# TOP.net
KiCad netlist of a schematic drawn in Altium Designer
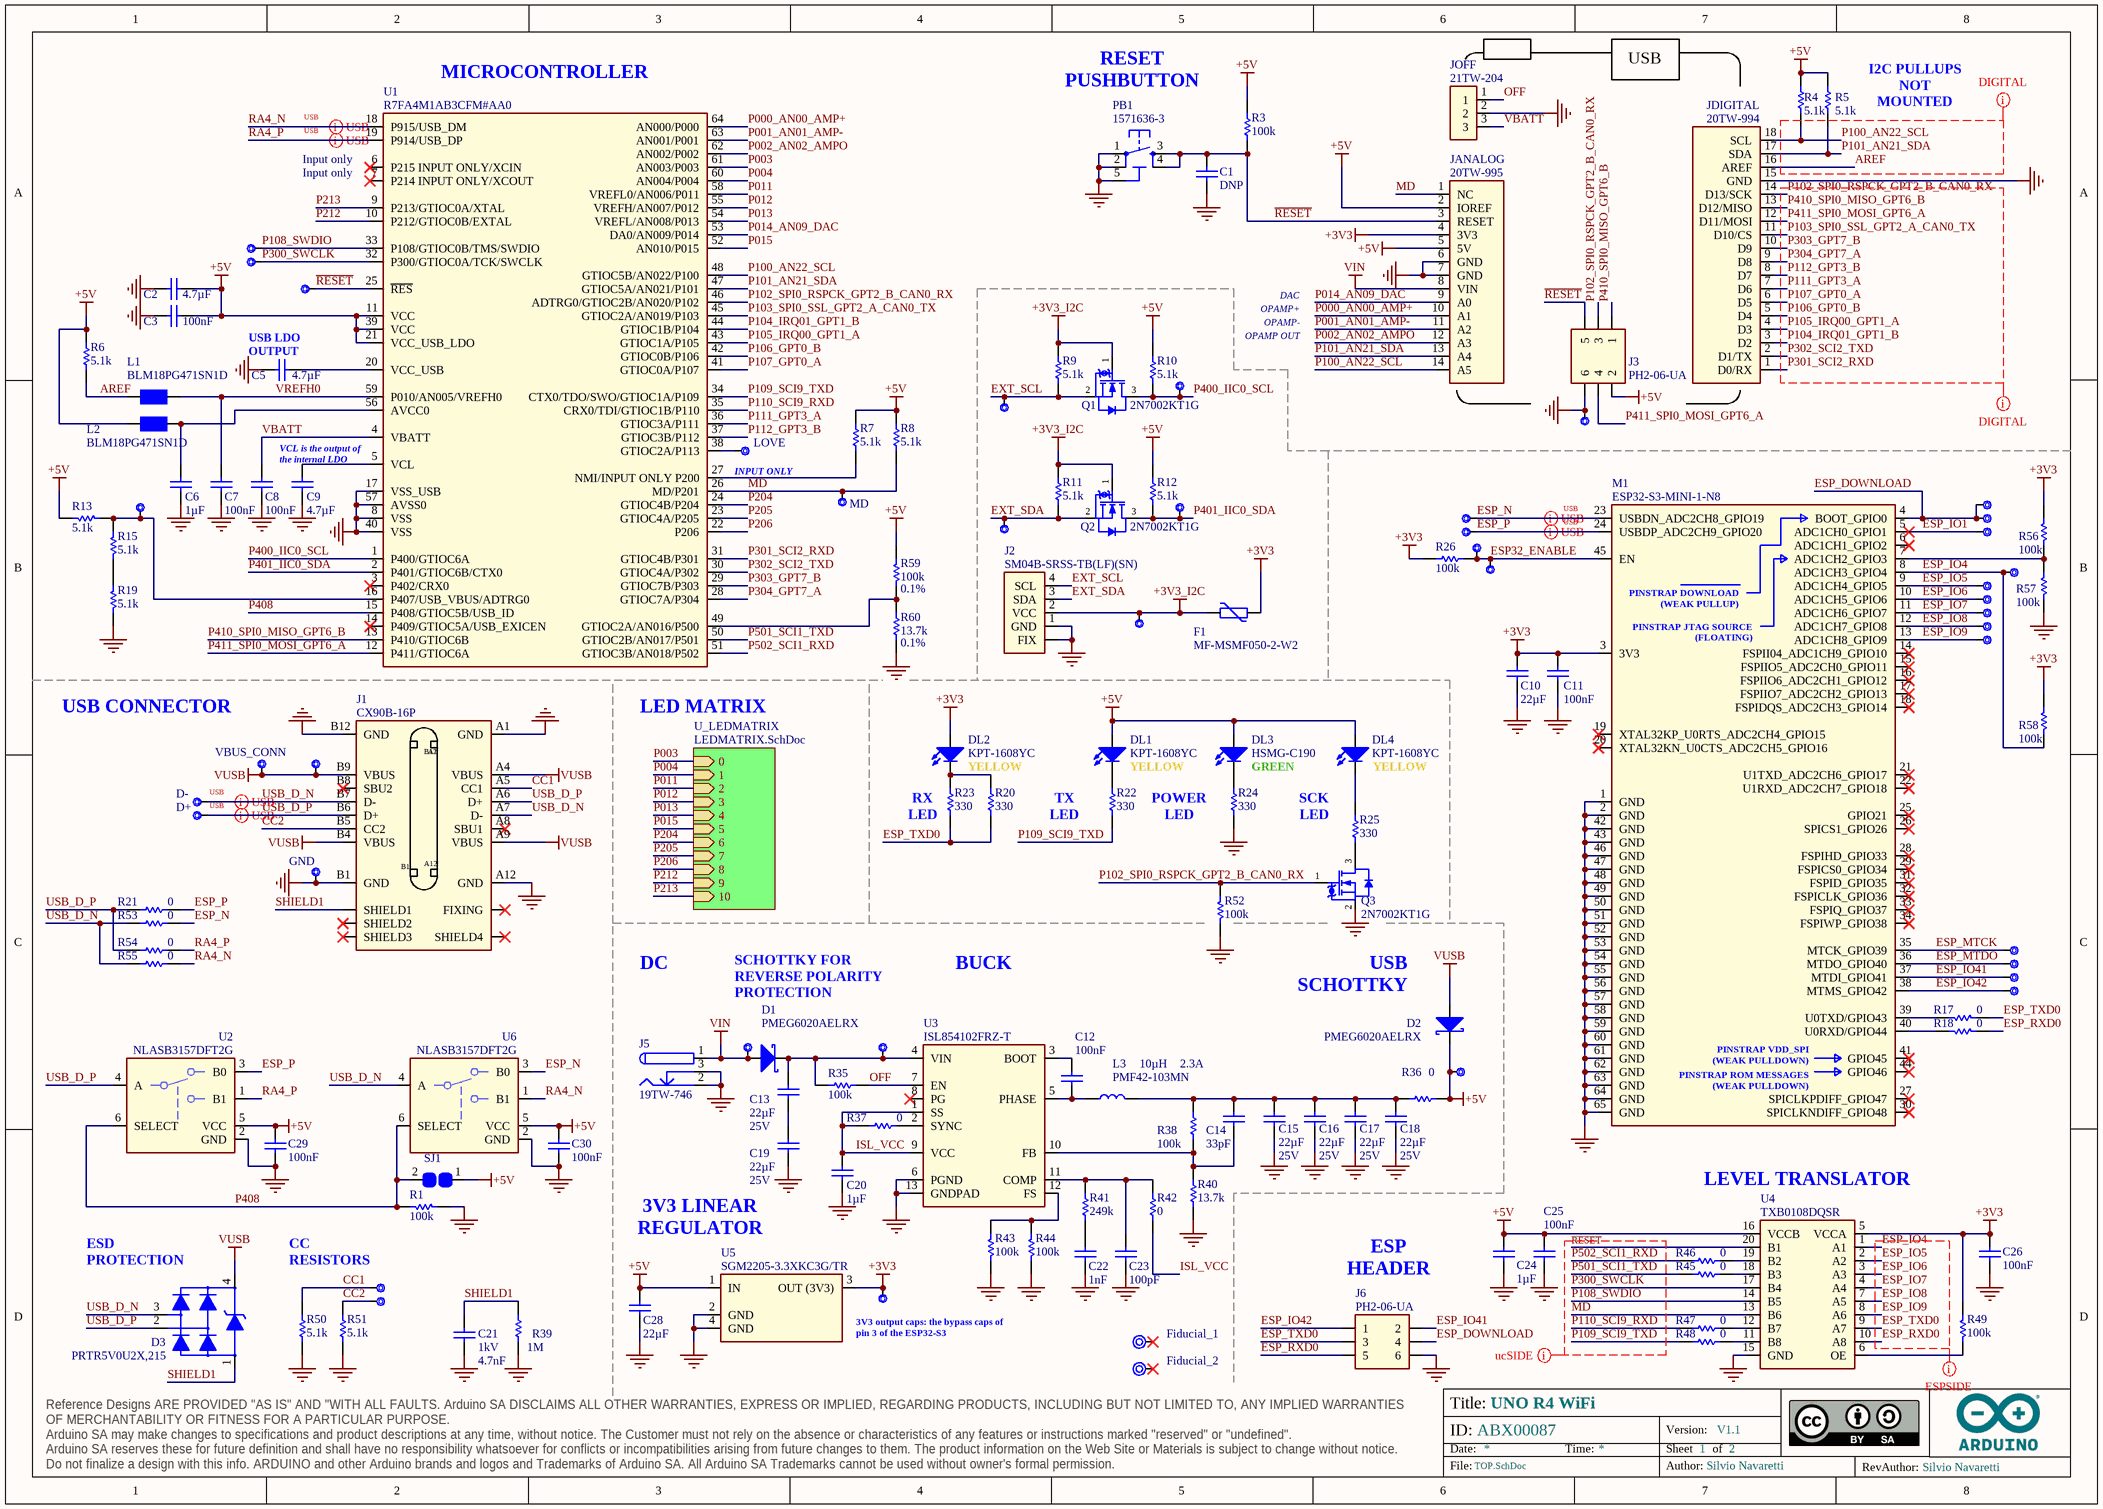
[diagram p0: TOP.SchDoc]

(export (version "E")
  (design (tool "Eeschema 10.0.6"))
  (components
    (comp (ref "3V3_IC")
      (value "CMP-018-0004-A.4")
      (footprint "TP-0.8MM")
      (description "Test point 0.8mm")
      (libsource (lib "Clean") (part "TESTPOINT"))
    )
    (comp (ref "3V3_TOP")
      (value "CMP-018-0004-A.4")
      (footprint "TP-0.8MM")
      (description "Test point 0.8mm")
      (libsource (lib "Clean") (part "TESTPOINT"))
    )
    (comp (ref "5V_TOP")
      (value "CMP-018-0004-A.4")
      (footprint "TP-0.8MM")
      (description "Test point 0.8mm")
      (libsource (lib "Clean") (part "TESTPOINT"))
    )
    (comp (ref "BUCK_IN_TOP")
      (value "CMP-018-0004-A.4")
      (footprint "TP-0.8MM")
      (description "Test point 0.8mm")
      (libsource (lib "Clean") (part "TESTPOINT"))
    )
    (comp (ref "C1") (value "DNP") (footprint "CAP-0402") (libsource (lib "Clean") (part "DNP")))
    (comp (ref "C2")
      (value "4.7µF")
      (footprint "CAP-0603")
      (description "CAP CHIP 0603 4.7uF 10% 16V X5R")
      (fields (field (name "TOLERANCE") "10%") (field (name "MANUFACTURER") "Murata"))
      (libsource (lib "Clean") (part "CAP"))
    )
    (comp (ref "C3")
      (value "100nF")
      (footprint "CAP-0402")
      (description "CAP CHIP 0402 100nF 10% 50V X5R")
      (fields (field (name "TOLERANCE") "10%") (field (name "MANUFACTURER") "Murata"))
      (libsource (lib "Clean") (part "CAP"))
    )
    (comp (ref "C5")
      (value "4.7µF")
      (footprint "CAP-0603")
      (description "CAP CHIP 0603 4.7uF 10% 16V X5R")
      (fields (field (name "TOLERANCE") "10%") (field (name "MANUFACTURER") "Murata"))
      (libsource (lib "Clean") (part "CAP"))
    )
    (comp (ref "C6")
      (value "1µF")
      (footprint "CAP-0402")
      (description "CAP CHIP 0402 1uF 10% 10V X5R")
      (fields (field (name "TOLERANCE") "10%") (field (name "PART NUMBER") "CL05A105KP5NNNC"))
      (libsource (lib "Clean") (part "CAP"))
    )
    (comp (ref "C7")
      (value "100nF")
      (footprint "CAP-0402")
      (description "CAP CHIP 0402 100nF 10% 50V X5R")
      (fields (field (name "TOLERANCE") "10%") (field (name "MANUFACTURER") "Murata"))
      (libsource (lib "Clean") (part "CAP"))
    )
    (comp (ref "C8")
      (value "100nF")
      (footprint "CAP-0402")
      (description "CAP CHIP 0402 100nF 10% 50V X5R")
      (fields (field (name "TOLERANCE") "10%") (field (name "MANUFACTURER") "Murata"))
      (libsource (lib "Clean") (part "CAP"))
    )
    (comp (ref "C9")
      (value "4.7µF")
      (footprint "CAP-0603")
      (description "CAP CHIP 0603 4.7uF 10% 16V X5R")
      (fields (field (name "TOLERANCE") "10%") (field (name "MANUFACTURER") "Murata"))
      (libsource (lib "Clean") (part "CAP"))
    )
    (comp (ref "C10")
      (value "22µF")
      (footprint "CAP-0805")
      (description "CAP CHIP 0805 22uF 20% 25V X5R")
      (fields (field (name "VOLTAGE") "25V") (field (name "TOLERANCE") "20%"))
      (libsource (lib "Clean") (part "CAP"))
    )
    (comp (ref "C11")
      (value "100nF")
      (footprint "CAP-0402")
      (description "CAP CHIP 0402 100nF 10% 50V X5R")
      (fields (field (name "TOLERANCE") "10%") (field (name "MANUFACTURER") "Murata"))
      (libsource (lib "Clean") (part "CAP"))
    )
    (comp (ref "C12")
      (value "100nF")
      (footprint "CAP-0402")
      (description "CAP CHIP 0402 100nF 10% 50V X5R")
      (fields (field (name "TOLERANCE") "10%") (field (name "MANUFACTURER") "Murata"))
      (libsource (lib "Clean") (part "CAP"))
    )
    (comp (ref "C13")
      (value "22µF")
      (footprint "CAP-0805")
      (description "CAP CHIP 0805 22uF 20% 25V X5R")
      (fields
        (field (name "PART NUMBER") "CL21A226MAQNNNE")
        (field (name "TOLERANCE") "20%")
        (field (name "VOLTAGE") "25V")
      )
      (libsource (lib "Clean") (part "CAP"))
    )
    (comp (ref "C14")
      (value "33pF")
      (footprint "CAP-0402")
      (description "CAP CHIP 0402 33pF 5% 50V C0G")
      (fields (field (name "MANUFACTURER") "Murata") (field (name "VOLTAGE") "50V"))
      (libsource (lib "Clean") (part "CAP"))
    )
    (comp (ref "C15")
      (value "22µF")
      (footprint "CAP-0805")
      (description "CAP CHIP 0805 22uF 20% 25V X5R")
      (fields
        (field (name "PART NUMBER") "CL21A226MAQNNNE")
        (field (name "TOLERANCE") "20%")
        (field (name "VOLTAGE") "25V")
      )
      (libsource (lib "Clean") (part "CAP"))
    )
    (comp (ref "C16")
      (value "22µF")
      (footprint "CAP-0805")
      (description "CAP CHIP 0805 22uF 20% 25V X5R")
      (fields
        (field (name "PART NUMBER") "CL21A226MAQNNNE")
        (field (name "TOLERANCE") "20%")
        (field (name "VOLTAGE") "25V")
      )
      (libsource (lib "Clean") (part "CAP"))
    )
    (comp (ref "C17")
      (value "22µF")
      (footprint "CAP-0805")
      (description "CAP CHIP 0805 22uF 20% 25V X5R")
      (fields
        (field (name "PART NUMBER") "CL21A226MAQNNNE")
        (field (name "TOLERANCE") "20%")
        (field (name "VOLTAGE") "25V")
      )
      (libsource (lib "Clean") (part "CAP"))
    )
    (comp (ref "C18")
      (value "22µF")
      (footprint "CAP-0805")
      (description "CAP CHIP 0805 22uF 20% 25V X5R")
      (fields
        (field (name "PART NUMBER") "CL21A226MAQNNNE")
        (field (name "TOLERANCE") "20%")
        (field (name "VOLTAGE") "25V")
      )
      (libsource (lib "Clean") (part "CAP"))
    )
    (comp (ref "C19")
      (value "22µF")
      (footprint "CAP-0805")
      (description "CAP CHIP 0805 22uF 20% 25V X5R")
      (fields
        (field (name "PART NUMBER") "CL21A226MAQNNNE")
        (field (name "TOLERANCE") "20%")
        (field (name "VOLTAGE") "25V")
      )
      (libsource (lib "Clean") (part "CAP"))
    )
    (comp (ref "C20")
      (value "1µF")
      (footprint "CAP-0402")
      (description "CAP CHIP 0402 1uF 10% 10V X5R")
      (fields (field (name "TOLERANCE") "10%") (field (name "PART NUMBER") "CL05A105KP5NNNC"))
      (libsource (lib "Clean") (part "CAP"))
    )
    (comp (ref "C21")
      (value "4.7nF")
      (footprint "CAP-0805")
      (description "CAP CHIP 0805 4.7nF 10% 1000V X7R")
      (fields
        (field (name "MANUFACTURER") "PSA Shenzen")
        (field (name "VOLTAGE") "1kV")
        (field (name "TOLERANCE") "10%")
      )
      (libsource (lib "Clean") (part "CAP"))
    )
    (comp (ref "C22")
      (value "1nF")
      (footprint "CAP-0402")
      (description "CAP CHIP 0402 1nF 10% 50V X7R")
      (fields (field (name "TOLERANCE") "10%") (field (name "MANUFACTURER") "KEMET"))
      (libsource (lib "Clean") (part "CAP"))
    )
    (comp (ref "C23")
      (value "100pF")
      (footprint "CAP-0402")
      (description "CAP CHIP 0402 100pF 10% 50V C0G")
      (fields (field (name "TOLERANCE") "5%") (field (name "MANUFACTURER") "Yageo"))
      (libsource (lib "Clean") (part "CAP"))
    )
    (comp (ref "C24")
      (value "1µF")
      (footprint "CAP-0402")
      (description "CAP CHIP 0402 1uF 10% 10V X5R")
      (fields (field (name "TOLERANCE") "10%") (field (name "PART NUMBER") "CL05A105KP5NNNC"))
      (libsource (lib "Clean") (part "CAP"))
    )
    (comp (ref "C25")
      (value "100nF")
      (footprint "CAP-0402")
      (description "CAP CHIP 0402 100nF 10% 50V X5R")
      (fields (field (name "TOLERANCE") "10%") (field (name "MANUFACTURER") "Murata"))
      (libsource (lib "Clean") (part "CAP"))
    )
    (comp (ref "C26")
      (value "100nF")
      (footprint "CAP-0402")
      (description "CAP CHIP 0402 100nF 10% 50V X5R")
      (fields (field (name "TOLERANCE") "10%") (field (name "MANUFACTURER") "Murata"))
      (libsource (lib "Clean") (part "CAP"))
    )
    (comp (ref "C28")
      (value "22µF")
      (footprint "CAP-0805")
      (description "CAP CHIP 0805 22uF 20% 25V X5R")
      (fields (field (name "VOLTAGE") "25V") (field (name "TOLERANCE") "20%"))
      (libsource (lib "Clean") (part "CAP"))
    )
    (comp (ref "C29")
      (value "100nF")
      (footprint "CAP-0402")
      (description "CAP CHIP 0402 100nF 10% 50V X5R")
      (fields (field (name "TOLERANCE") "10%") (field (name "MANUFACTURER") "Murata"))
      (libsource (lib "Clean") (part "CAP"))
    )
    (comp (ref "C30")
      (value "100nF")
      (footprint "CAP-0402")
      (description "CAP CHIP 0402 100nF 10% 50V X5R")
      (fields (field (name "TOLERANCE") "10%") (field (name "MANUFACTURER") "Murata"))
      (libsource (lib "Clean") (part "CAP"))
    )
    (comp (ref "CC1")
      (value "CMP-018-0004-A.4")
      (footprint "TP-0.8MM")
      (description "Test point 0.8mm")
      (libsource (lib "Clean") (part "TESTPOINT"))
    )
    (comp (ref "CC2")
      (value "CMP-018-0004-A.4")
      (footprint "TP-0.8MM")
      (description "Test point 0.8mm")
      (libsource (lib "Clean") (part "TESTPOINT"))
    )
    (comp (ref "D+")
      (value "CMP-018-0005-A.3")
      (footprint "TP-1.00MM")
      (description "Test point 1.00mm")
      (libsource (lib "Clean") (part "TESTPOINT"))
    )
    (comp (ref "D+_TOP")
      (value "CMP-018-0004-A.4")
      (footprint "TP-0.8MM")
      (description "Test point 0.8mm")
      (libsource (lib "Clean") (part "TESTPOINT"))
    )
    (comp (ref "D-")
      (value "CMP-018-0005-A.3")
      (footprint "TP-1.00MM")
      (description "Test point 1.00mm")
      (libsource (lib "Clean") (part "TESTPOINT"))
    )
    (comp (ref "D-_TOP")
      (value "CMP-018-0004-A.4")
      (footprint "TP-0.8MM")
      (description "Test point 0.8mm")
      (libsource (lib "Clean") (part "TESTPOINT"))
    )
    (comp (ref "D1")
      (value "PMEG6020AELRX")
      (footprint "SOD123-1")
      (description "DIODE SCHOTTKY SMD 2A 60V SOD123FL")
      (fields (field (name "MANUFACTURER") "Nexperia"))
      (libsource (lib "Clean") (part "PMEG6020AELRX"))
    )
    (comp (ref "D2")
      (value "PMEG6020AELRX")
      (footprint "SOD123-1")
      (description "DIODE SCHOTTKY SMD 2A 60V SOD123FL")
      (fields (field (name "MANUFACTURER") "Nexperia"))
      (libsource (lib "Clean") (part "PMEG6020AELRX"))
    )
    (comp (ref "D3")
      (value "PRTR5V0U2X,215")
      (footprint "SOT190P230X110-4N")
      (description "TVS ARRAY 4LIN.8kV 1pF SOT143B")
      (fields (field (name "MANUFACTURER") "Nexperia"))
      (libsource (lib "Clean") (part "PRTR5V0U2X,215"))
    )
    (comp (ref "DL1")
      (value "KPT-1608YC")
      (footprint "LEDC1608X80N-AK")
      (description "LED SMD 0603 GIA588   8mcd 120^")
      (fields (field (name "MANUFACTURER") "Kingbright"))
      (libsource (lib "Clean") (part "LED"))
    )
    (comp (ref "DL2")
      (value "KPT-1608YC")
      (footprint "LEDC1608X80N-AK")
      (description "LED SMD 0603 GIA588   8mcd 120^")
      (fields (field (name "MANUFACTURER") "Kingbright"))
      (libsource (lib "Clean") (part "LED"))
    )
    (comp (ref "DL3")
      (value "HSMG-C190")
      (footprint "LEDC1608X80N-AK")
      (description "LED SMD 0603 GREEN/568 15mcd 120^")
      (fields (field (name "MANUFACTURER") "Broadcom"))
      (libsource (lib "Clean") (part "LED"))
    )
    (comp (ref "DL4")
      (value "KPT-1608YC")
      (footprint "LEDC1608X80N-AK")
      (description "LED SMD 0603 GIA588   8mcd 120^")
      (fields (field (name "MANUFACTURER") "Kingbright"))
      (libsource (lib "Clean") (part "LED"))
    )
    (comp (ref "ESP_DOWNLOAD_BOTTOM1")
      (value "CMP-018-0005-A.3")
      (footprint "TP-1.00MM")
      (description "Test point 1.00mm")
      (libsource (lib "Clean") (part "TESTPOINT"))
    )
    (comp (ref "ESP_DOWNLOAD_TOP")
      (value "CMP-018-0004-A.4")
      (footprint "TP-0.8MM")
      (description "Test point 0.8mm")
      (libsource (lib "Clean") (part "TESTPOINT"))
    )
    (comp (ref "ESP_EN_BOTTOM")
      (value "CMP-018-0005-A.3")
      (footprint "TP-1.00MM")
      (description "Test point 1.00mm")
      (libsource (lib "Clean") (part "TESTPOINT"))
    )
    (comp (ref "ESP_EN_TOP")
      (value "CMP-018-0004-A.4")
      (footprint "TP-0.8MM")
      (description "Test point 0.8mm")
      (libsource (lib "Clean") (part "TESTPOINT"))
    )
    (comp (ref "ESP_IO1")
      (value "CMP-018-0004-A.4")
      (footprint "TP-0.8MM")
      (description "Test point 0.8mm")
      (libsource (lib "Clean") (part "TESTPOINT"))
    )
    (comp (ref "ESP_IO4")
      (value "CMP-018-0004-A.4")
      (footprint "TP-0.8MM")
      (description "Test point 0.8mm")
      (libsource (lib "Clean") (part "TESTPOINT"))
    )
    (comp (ref "ESP_IO5")
      (value "CMP-018-0004-A.4")
      (footprint "TP-0.8MM")
      (description "Test point 0.8mm")
      (libsource (lib "Clean") (part "TESTPOINT"))
    )
    (comp (ref "ESP_IO6")
      (value "CMP-018-0004-A.4")
      (footprint "TP-0.8MM")
      (description "Test point 0.8mm")
      (libsource (lib "Clean") (part "TESTPOINT"))
    )
    (comp (ref "ESP_IO7")
      (value "CMP-018-0004-A.4")
      (footprint "TP-0.8MM")
      (description "Test point 0.8mm")
      (libsource (lib "Clean") (part "TESTPOINT"))
    )
    (comp (ref "ESP_IO8")
      (value "CMP-018-0004-A.4")
      (footprint "TP-0.8MM")
      (description "Test point 0.8mm")
      (libsource (lib "Clean") (part "TESTPOINT"))
    )
    (comp (ref "ESP_IO9")
      (value "CMP-018-0004-A.4")
      (footprint "TP-0.8MM")
      (description "Test point 0.8mm")
      (libsource (lib "Clean") (part "TESTPOINT"))
    )
    (comp (ref "ESP_MTCK")
      (value "CMP-018-0004-A.4")
      (footprint "TP-0.8MM")
      (description "Test point 0.8mm")
      (libsource (lib "Clean") (part "TESTPOINT"))
    )
    (comp (ref "ESP_MTDI")
      (value "CMP-018-0004-A.4")
      (footprint "TP-0.8MM")
      (description "Test point 0.8mm")
      (libsource (lib "Clean") (part "TESTPOINT"))
    )
    (comp (ref "ESP_MTDO")
      (value "CMP-018-0004-A.4")
      (footprint "TP-0.8MM")
      (description "Test point 0.8mm")
      (libsource (lib "Clean") (part "TESTPOINT"))
    )
    (comp (ref "ESP_MTMS")
      (value "CMP-018-0004-A.4")
      (footprint "TP-0.8MM")
      (description "Test point 0.8mm")
      (libsource (lib "Clean") (part "TESTPOINT"))
    )
    (comp (ref "EXT_SCL")
      (value "CMP-018-0004-A.4")
      (footprint "TP-0.8MM")
      (description "Test point 0.8mm")
      (libsource (lib "Clean") (part "TESTPOINT"))
    )
    (comp (ref "EXT_SDA")
      (value "CMP-018-0004-A.4")
      (footprint "TP-0.8MM")
      (description "Test point 0.8mm")
      (libsource (lib "Clean") (part "TESTPOINT"))
    )
    (comp (ref "F1")
      (value "MF-MSMF050-2-W2")
      (footprint "1812")
      (description "PTC RESET FUSE 15V 500MA 1812 LOGO OO ARDUINO")
      (fields (field (name "MANUFACTURER") "Bourns"))
      (libsource (lib "Clean") (part "Symbol"))
    )
    (comp (ref "Fiducial_1")
      (value "Fiducial mark 1mm with 2mm solder")
      (footprint "Fiducial mark 1mm with circle-Footprint-1")
      (libsource (lib "Clean") (part "Fiducial mark 1mm with circle"))
    )
    (comp (ref "Fiducial_2")
      (value "Fiducial mark 1mm with 2mm solder")
      (footprint "Fiducial mark 1mm with circle-Footprint-1")
      (libsource (lib "Clean") (part "Fiducial mark 1mm with circle"))
    )
    (comp (ref "GND")
      (value "CMP-018-0005-A.3")
      (footprint "TP-1.00MM")
      (description "Test point 1.00mm")
      (libsource (lib "Clean") (part "TESTPOINT"))
    )
    (comp (ref "GND2")
      (value "CMP-018-0005-A.3")
      (footprint "TP-1.00MM")
      (description "Test point 1.00mm")
      (libsource (lib "Clean") (part "TESTPOINT"))
    )
    (comp (ref "J1")
      (value "CX90B-16P")
      (footprint "CX90B-16P-Footprint-1")
      (description "CONN RCPT USB3.1 TYPEC 16POS SMD")
      (fields (field (name "MANUFACTURER") "Hirose"))
      (libsource (lib "Clean") (part "CX90B-16P-Symbol-1"))
    )
    (comp (ref "J2")
      (value "SM04B-SRSS-TB(LF)(SN)")
      (footprint "SM04B-SRSS-TB(LF)(SN)-Footprint-1")
      (description "CONN JST 4POS SIDE 1MM TIN QWIIC")
      (fields (field (name "MANUFACTURER") "JST"))
      (libsource (lib "Clean") (part "SM04B-SRSS-TB(LF)(SN)"))
    )
    (comp (ref "J3")
      (value "PH2-06-UA")
      (footprint "2X03")
      (description "CONN Header Through Hole 6 position 0.100\" (2.54mm)")
      (fields (field (name "MANUFACTURER") "Adam Tech"))
      (libsource (lib "") (part "PH2-06-UA_1"))
    )
    (comp (ref "J5")
      (value "19TW-746")
      (footprint "POWERSUPPLY_DC-21MM")
      (description "CONN PWR JACK 2.1X5.5MM SOLDER")
      (fields (field (name "MANUFACTURER") "4UCON"))
      (libsource (lib "Clean") (part "19TW-746"))
    )
    (comp (ref "J6")
      (value "PH2-06-UA")
      (footprint "2X03")
      (description "CONN Header Through Hole 6 position 0.100\" (2.54mm)")
      (fields (field (name "MANUFACTURER") "Adam Tech"))
      (libsource (lib "Clean") (part "PH2-06-UA"))
    )
    (comp (ref "JANALOG")
      (value "20TW-995")
      (footprint "1X14-CUSTOM")
      (description "CONN STRIP F/1/D 14v SER.NERA s1pin")
      (fields (field (name "MANUFACTURER") "4UCONN"))
      (libsource (lib "Clean") (part "20TW-995"))
    )
    (comp (ref "JDIGITAL")
      (value "20TW-994")
      (footprint "1X18-CUSTOM")
      (description "CONN STRIP F/1/D 18v SER.NERA s1pin")
      (fields (field (name "MANUFACTURER") "4UCONN"))
      (libsource (lib "Clean") (part "20TW-994"))
    )
    (comp (ref "JOFF")
      (value "21TW-204")
      (footprint "21TW-204")
      (description "CONN HEADER VERT 3POS 2.54MM")
      (fields (field (name "MANUFACTURER") "4UCONN"))
      (libsource (lib "Clean") (part "21TW-204"))
    )
    (comp (ref "L1")
      (value "BLM18PG471SN1D")
      (footprint "L-0603")
      (description "FERRITE SMD 0603 470R 1A 0.2R")
      (fields (field (name "TOLERANCE") "25%") (field (name "MANUFACTURER") "Murata"))
      (libsource (lib "Clean") (part "Ferrite"))
    )
    (comp (ref "L2")
      (value "BLM18PG471SN1D")
      (footprint "L-0603")
      (description "FERRITE SMD 0603 470R 1A 0.2R")
      (fields (field (name "TOLERANCE") "25%") (field (name "MANUFACTURER") "Murata"))
      (libsource (lib "Clean") (part "Ferrite"))
    )
    (comp (ref "L3")
      (value "PMF42-103MN")
      (footprint "PMF42")
      (description "IND 10uH 20%, max 235mR, IDC 2.3A, Isat 2.3A, shielded, max 5MHz, 4.5x4.5x1.8mm")
      (fields
        (field (name "MAX DC CURRENT") "2.3A")
        (field (name "INDUCTANCE") "10µH")
        (field (name "TOLERANCE") "20%")
        (field (name "MANUFACTURER") "K-WELL")
      )
      (libsource (lib "Clean") (part "Inductor"))
    )
    (comp (ref "LOVE")
      (value "CMP-018-0005-A.3")
      (footprint "TP-1.00MM")
      (description "Test point 1.00mm")
      (libsource (lib "Clean") (part "TESTPOINT"))
    )
    (comp (ref "M1")
      (value "ESP32-S3-MINI-1-N8")
      (footprint "ESP32-S3-MINI-1-N8")
      (fields (field (name "MANUFACTURER") "Espressif"))
      (libsource (lib "Clean") (part "ESP32-S3-MINI-1-N8"))
    )
    (comp (ref "MD")
      (value "CMP-018-0004-A.4")
      (footprint "TP-0.8MM")
      (description "Test point 0.8mm")
      (libsource (lib "Clean") (part "TESTPOINT"))
    )
    (comp (ref "P400_SCL")
      (value "CMP-018-0004-A.4")
      (footprint "TP-0.8MM")
      (description "Test point 0.8mm")
      (libsource (lib "Clean") (part "TESTPOINT"))
    )
    (comp (ref "P401_SDA")
      (value "CMP-018-0004-A.4")
      (footprint "TP-0.8MM")
      (description "Test point 0.8mm")
      (libsource (lib "Clean") (part "TESTPOINT"))
    )
    (comp (ref "PB1")
      (value "1571636-3")
      (footprint "TS42")
      (description "PUSHBUTTON SMD 6x6 5 PINS")
      (fields (field (name "MANUFACTURER") "TE Connectivity"))
      (libsource (lib "Clean") (part "PB6X6_5P"))
    )
    (comp (ref "Q1")
      (value "2N7002KT1G")
      (footprint "SOT23")
      (description "MOSFET N-CH 60V 300mA ESD prot. SOT23")
      (fields (field (name "MANUFACTURER") "On Semiconductor"))
      (libsource (lib "Clean") (part "NMOS-2"))
    )
    (comp (ref "Q2")
      (value "2N7002KT1G")
      (footprint "SOT23")
      (description "MOSFET N-CH 60V 300mA ESD prot. SOT23")
      (fields (field (name "MANUFACTURER") "On Semiconductor"))
      (libsource (lib "Clean") (part "NMOS-2"))
    )
    (comp (ref "Q3")
      (value "2N7002KT1G")
      (footprint "SOT23")
      (description "MOSFET N-CH 60V 300mA ESD prot. SOT23")
      (fields (field (name "MANUFACTURER") "On Semiconductor"))
      (libsource (lib "Clean") (part "NMOS-2"))
    )
    (comp (ref "R1")
      (value "100k")
      (footprint "RES-0402")
      (description "RES CHIP 0402 100k 1% 1/16W")
      (fields (field (name "PART NUMBER") "CRCW0402100KFKEDC") (field (name "MANUFACTURER") "Vishay"))
      (libsource (lib "Clean") (part "RES"))
    )
    (comp (ref "R3")
      (value "100k")
      (footprint "RES-0402")
      (description "RES CHIP 0402 100k 1% 1/16W")
      (fields (field (name "PART NUMBER") "CRCW0402100KFKEDC") (field (name "MANUFACTURER") "Vishay"))
      (libsource (lib "Clean") (part "RES"))
    )
    (comp (ref "R4")
      (value "5.1k")
      (footprint "RES-0402")
      (description "RES CHIP 0402 5k1 1% 1/16W")
      (fields (field (name "TOLERANCE") "1%") (field (name "POWER") "63mW"))
      (libsource (lib "Clean") (part "RES"))
    )
    (comp (ref "R5")
      (value "5.1k")
      (footprint "RES-0402")
      (description "RES CHIP 0402 5k1 1% 1/16W")
      (fields (field (name "TOLERANCE") "1%") (field (name "POWER") "63mW"))
      (libsource (lib "Clean") (part "RES"))
    )
    (comp (ref "R6")
      (value "5.1k")
      (footprint "RES-0402")
      (description "RES CHIP 0402 5k1 1% 1/16W")
      (fields (field (name "TOLERANCE") "1%") (field (name "POWER") "63mW"))
      (libsource (lib "Clean") (part "RES"))
    )
    (comp (ref "R7")
      (value "5.1k")
      (footprint "RES-0402")
      (description "RES CHIP 0402 5k1 1% 1/16W")
      (fields (field (name "TOLERANCE") "1%") (field (name "MANUFACTURER") "YAGEO"))
      (libsource (lib "Clean") (part "RES"))
    )
    (comp (ref "R8")
      (value "5.1k")
      (footprint "RES-0402")
      (description "RES CHIP 0402 5k1 1% 1/16W")
      (fields (field (name "TOLERANCE") "1%") (field (name "MANUFACTURER") "YAGEO"))
      (libsource (lib "Clean") (part "RES"))
    )
    (comp (ref "R9")
      (value "5.1k")
      (footprint "RES-0402")
      (description "RES CHIP 0402 5k1 1% 1/16W")
      (fields (field (name "TOLERANCE") "1%") (field (name "MANUFACTURER") "YAGEO"))
      (libsource (lib "Clean") (part "RES"))
    )
    (comp (ref "R10")
      (value "5.1k")
      (footprint "RES-0402")
      (description "RES CHIP 0402 5k1 1% 1/16W")
      (fields (field (name "TOLERANCE") "1%") (field (name "MANUFACTURER") "YAGEO"))
      (libsource (lib "Clean") (part "RES"))
    )
    (comp (ref "R11")
      (value "5.1k")
      (footprint "RES-0402")
      (description "RES CHIP 0402 5k1 1% 1/16W")
      (fields (field (name "TOLERANCE") "1%") (field (name "MANUFACTURER") "YAGEO"))
      (libsource (lib "Clean") (part "RES"))
    )
    (comp (ref "R12")
      (value "5.1k")
      (footprint "RES-0402")
      (description "RES CHIP 0402 5k1 1% 1/16W")
      (fields (field (name "TOLERANCE") "1%") (field (name "MANUFACTURER") "YAGEO"))
      (libsource (lib "Clean") (part "RES"))
    )
    (comp (ref "R13")
      (value "5.1k")
      (footprint "RES-0402")
      (description "RES CHIP 0402 5k1 1% 1/16W")
      (fields (field (name "TOLERANCE") "1%") (field (name "POWER") "63mW"))
      (libsource (lib "Clean") (part "RES"))
    )
    (comp (ref "R15")
      (value "5.1k")
      (footprint "RES-0402")
      (description "RES CHIP 0402 5k1 1% 1/16W")
      (fields (field (name "TOLERANCE") "1%") (field (name "POWER") "63mW"))
      (libsource (lib "Clean") (part "RES"))
    )
    (comp (ref "R17")
      (value "0")
      (footprint "RES-0402")
      (description "RES CHIP 0402 0R 1/16W")
      (fields (field (name "POWER") "62.5mW") (field (name "TOLERANCE") "0%"))
      (libsource (lib "Clean") (part "RES"))
    )
    (comp (ref "R18")
      (value "0")
      (footprint "RES-0402")
      (description "RES CHIP 0402 0R 1/16W")
      (fields (field (name "POWER") "62.5mW") (field (name "TOLERANCE") "0%"))
      (libsource (lib "Clean") (part "RES"))
    )
    (comp (ref "R19")
      (value "5.1k")
      (footprint "RES-0402")
      (description "RES CHIP 0402 5k1 1% 1/16W")
      (fields (field (name "TOLERANCE") "1%") (field (name "POWER") "63mW"))
      (libsource (lib "Clean") (part "RES"))
    )
    (comp (ref "R20")
      (value "330")
      (footprint "RES-0402")
      (description "RES CHIP 0402 330R 5% 1/16W")
      (fields (field (name "PART NUMBER") "CRCW0402330RJNED") (field (name "TOLERANCE") "5%"))
      (libsource (lib "Clean") (part "RES"))
    )
    (comp (ref "R21")
      (value "0")
      (footprint "RES-0402")
      (description "RES CHIP 0402 0R 1/16W")
      (fields (field (name "POWER") "62.5mW") (field (name "TOLERANCE") "0%"))
      (libsource (lib "Clean") (part "RES"))
    )
    (comp (ref "R22")
      (value "330")
      (footprint "RES-0402")
      (description "RES CHIP 0402 330R 5% 1/16W")
      (fields (field (name "PART NUMBER") "CRCW0402330RJNED") (field (name "TOLERANCE") "5%"))
      (libsource (lib "Clean") (part "RES"))
    )
    (comp (ref "R23")
      (value "330")
      (footprint "RES-0402")
      (description "RES CHIP 0402 330R 5% 1/16W")
      (fields (field (name "PART NUMBER") "CRCW0402330RJNED") (field (name "TOLERANCE") "5%"))
      (libsource (lib "Clean") (part "RES"))
    )
    (comp (ref "R24")
      (value "330")
      (footprint "RES-0402")
      (description "RES CHIP 0402 330R 5% 1/16W")
      (fields (field (name "PART NUMBER") "CRCW0402330RJNED") (field (name "TOLERANCE") "5%"))
      (libsource (lib "Clean") (part "RES"))
    )
    (comp (ref "R25")
      (value "330")
      (footprint "RES-0402")
      (description "RES CHIP 0402 330R 5% 1/16W")
      (fields (field (name "PART NUMBER") "CRCW0402330RJNED") (field (name "TOLERANCE") "5%"))
      (libsource (lib "Clean") (part "RES"))
    )
    (comp (ref "R26")
      (value "100k")
      (footprint "RES-0402")
      (description "RES CHIP 0402 100k 1% 1/16W")
      (fields (field (name "TOLERANCE") "1%") (field (name "MANUFACTURER") "Vishay"))
      (libsource (lib "Clean") (part "RES"))
    )
    (comp (ref "R35")
      (value "100k")
      (footprint "RES-0402")
      (description "RES CHIP 0402 100k 1% 1/16W")
      (fields (field (name "TOLERANCE") "1%") (field (name "MANUFACTURER") "Vishay"))
      (libsource (lib "Clean") (part "RES"))
    )
    (comp (ref "R36")
      (value "0")
      (footprint "RES-0402")
      (description "RES CHIP 0402 0R 1/16W")
      (fields (field (name "MANUFACTURER") "Vishay") (field (name "PART NUMBER") "CRCW04020000Z0EDC"))
      (libsource (lib "Clean") (part "RES"))
    )
    (comp (ref "R37")
      (value "0")
      (footprint "RES-0402")
      (description "RES CHIP 0402 0R 1/16W")
      (fields (field (name "POWER") "62.5mW") (field (name "TOLERANCE") "0%"))
      (libsource (lib "Clean") (part "RES"))
    )
    (comp (ref "R38")
      (value "100k")
      (footprint "RES-0402")
      (description "RES CHIP 0402 100k 1% 1/16W")
      (fields (field (name "TOLERANCE") "1%") (field (name "MANUFACTURER") "Vishay"))
      (libsource (lib "Clean") (part "RES"))
    )
    (comp (ref "R39")
      (value "1M")
      (footprint "RES-0402")
      (description "RES CHIP 0402 1M 1% 1/16W")
      (fields (field (name "MANUFACTURER") "Vishay") (field (name "POWER") "62.5mW"))
      (libsource (lib "Clean") (part "RES"))
    )
    (comp (ref "R40")
      (value "13.7k")
      (footprint "RES-0402")
      (description "RES CHIP 0402 13k7 1% 1/16W")
      (fields (field (name "MANUFACTURER") "YAGEO") (field (name "TOLERANCE") "1%"))
      (libsource (lib "Clean") (part "RES"))
    )
    (comp (ref "R41")
      (value "249k")
      (footprint "RES-0402")
      (description "RES CHIP 0402 249k 1% 1/16W")
      (fields (field (name "TOLERANCE") "1%") (field (name "PART NUMBER") "AC0402FR-07249KL"))
      (libsource (lib "Clean") (part "RES"))
    )
    (comp (ref "R42")
      (value "0")
      (footprint "RES-0402")
      (description "RES CHIP 0402 0R 1/16W")
      (fields (field (name "POWER") "62.5mW") (field (name "TOLERANCE") "0%"))
      (libsource (lib "Clean") (part "RES"))
    )
    (comp (ref "R43")
      (value "100k")
      (footprint "RES-0402")
      (description "RES CHIP 0402 100k 1% 1/16W")
      (fields (field (name "PART NUMBER") "CRCW0402100KFKEDC") (field (name "MANUFACTURER") "Vishay"))
      (libsource (lib "Clean") (part "RES"))
    )
    (comp (ref "R44")
      (value "100k")
      (footprint "RES-0402")
      (description "RES CHIP 0402 100k 1% 1/16W")
      (fields (field (name "PART NUMBER") "CRCW0402100KFKEDC") (field (name "MANUFACTURER") "Vishay"))
      (libsource (lib "Clean") (part "RES"))
    )
    (comp (ref "R45")
      (value "0")
      (footprint "RES-0402")
      (description "RES CHIP 0402 0R 1/16W")
      (fields (field (name "POWER") "62.5mW") (field (name "TOLERANCE") "0%"))
      (libsource (lib "Clean") (part "RES"))
    )
    (comp (ref "R46")
      (value "0")
      (footprint "RES-0402")
      (description "RES CHIP 0402 0R 1/16W")
      (fields (field (name "POWER") "62.5mW") (field (name "TOLERANCE") "0%"))
      (libsource (lib "Clean") (part "RES"))
    )
    (comp (ref "R47")
      (value "0")
      (footprint "RES-0402")
      (description "RES CHIP 0402 0R 1/16W")
      (fields (field (name "POWER") "62.5mW") (field (name "TOLERANCE") "0%"))
      (libsource (lib "Clean") (part "RES"))
    )
    (comp (ref "R48")
      (value "0")
      (footprint "RES-0402")
      (description "RES CHIP 0402 0R 1/16W")
      (fields (field (name "POWER") "62.5mW") (field (name "TOLERANCE") "0%"))
      (libsource (lib "Clean") (part "RES"))
    )
    (comp (ref "R49")
      (value "100k")
      (footprint "RES-0402")
      (description "RES CHIP 0402 100k 1% 1/16W")
      (fields (field (name "PART NUMBER") "CRCW0402100KFKEDC") (field (name "MANUFACTURER") "Vishay"))
      (libsource (lib "Clean") (part "RES"))
    )
    (comp (ref "R50")
      (value "5.1k")
      (footprint "RES-0402")
      (description "RES CHIP 0402 5k1 1% 1/16W")
      (fields (field (name "PART NUMBER") "RC0402FR-075K1L") (field (name "MANUFACTURER") "YAGEO"))
      (libsource (lib "Clean") (part "RES"))
    )
    (comp (ref "R51")
      (value "5.1k")
      (footprint "RES-0402")
      (description "RES CHIP 0402 5k1 1% 1/16W")
      (fields (field (name "PART NUMBER") "RC0402FR-075K1L") (field (name "MANUFACTURER") "YAGEO"))
      (libsource (lib "Clean") (part "RES"))
    )
    (comp (ref "R52")
      (value "100k")
      (footprint "RES-0402")
      (description "RES CHIP 0402 100k 1% 1/16W")
      (fields (field (name "PART NUMBER") "CRCW0402100KFKEDC") (field (name "MANUFACTURER") "Vishay"))
      (libsource (lib "Clean") (part "RES"))
    )
    (comp (ref "R53")
      (value "0")
      (footprint "RES-0402")
      (description "RES CHIP 0402 0R 1/16W")
      (fields (field (name "POWER") "62.5mW") (field (name "TOLERANCE") "0%"))
      (libsource (lib "Clean") (part "RES"))
    )
    (comp (ref "R54")
      (value "0")
      (footprint "RES-0402")
      (description "RES CHIP 0402 0R 1/16W")
      (fields (field (name "POWER") "62.5mW") (field (name "TOLERANCE") "0%"))
      (libsource (lib "Clean") (part "RES"))
    )
    (comp (ref "R55")
      (value "0")
      (footprint "RES-0402")
      (description "RES CHIP 0402 0R 1/16W")
      (fields (field (name "POWER") "62.5mW") (field (name "TOLERANCE") "0%"))
      (libsource (lib "Clean") (part "RES"))
    )
    (comp (ref "R56")
      (value "100k")
      (footprint "RES-0402")
      (description "RES CHIP 0402 100k 1% 1/16W")
      (fields (field (name "PART NUMBER") "CRCW0402100KFKEDC") (field (name "MANUFACTURER") "Vishay"))
      (libsource (lib "Clean") (part "RES"))
    )
    (comp (ref "R57")
      (value "100k")
      (footprint "RES-0402")
      (description "RES CHIP 0402 100k 1% 1/16W")
      (fields (field (name "PART NUMBER") "CRCW0402100KFKEDC") (field (name "MANUFACTURER") "Vishay"))
      (libsource (lib "Clean") (part "RES"))
    )
    (comp (ref "R58")
      (value "100k")
      (footprint "RES-0402")
      (description "RES CHIP 0402 100k 1% 1/16W")
      (fields (field (name "PART NUMBER") "CRCW0402100KFKEDC") (field (name "MANUFACTURER") "Vishay"))
      (libsource (lib "Clean") (part "RES"))
    )
    (comp (ref "R59")
      (value "100k")
      (footprint "RES-0402")
      (description "RES CHIP 0402 100k 0.1% 100ppm 1/16W")
      (fields
        (field (name "PART NUMBER") "WF04H1003BT")
        (field (name "MANUFACTURER") "Walsin")
        (field (name "TOLERANCE") "0.1%")
      )
      (libsource (lib "Clean") (part "RES"))
    )
    (comp (ref "R60")
      (value "13.7k")
      (footprint "RES-0402")
      (description "RES CHIP 0402 13k7 0.1% 100PPM 1/16W")
      (fields
        (field (name "MANUFACTURER") "Walsin")
        (field (name "TOLERANCE") "0.1%")
        (field (name "POWER") "62.5mW")
      )
      (libsource (lib "Clean") (part "RES"))
    )
    (comp (ref "RES")
      (value "CMP-018-0004-A.4")
      (footprint "TP-0.8MM")
      (description "Test point 0.8mm")
      (libsource (lib "Clean") (part "TESTPOINT"))
    )
    (comp (ref "SJ1")
      (value "SMD solder JUMPER 0805")
      (footprint "SJ")
      (description "Solder Jumper 0805 THIS IS NOT A COMPONENT")
      (libsource (lib "Clean") (part "SJ"))
    )
    (comp (ref "SWCLK")
      (value "CMP-018-0004-A.4")
      (footprint "TP-0.8MM")
      (description "Test point 0.8mm")
      (libsource (lib "Clean") (part "TESTPOINT"))
    )
    (comp (ref "SWDIO")
      (value "CMP-018-0004-A.4")
      (footprint "TP-0.8MM")
      (description "Test point 0.8mm")
      (libsource (lib "Clean") (part "TESTPOINT"))
    )
    (comp (ref "U1")
      (value "R7FA4M1AB3CFM#AA0")
      (footprint "CQFP50P1200X1200X170-64L")
      (description "IC uC RA4M1 32b M4 48MHz 254KB flash 32KB RAM 105°C LQFP64 10x10mm")
      (fields (field (name "MANUFACTURER") "Renesas"))
      (libsource (lib "Clean") (part "R7FA4M1AB3CFM#AC0"))
    )
    (comp (ref "U2")
      (value "NLASB3157DFT2G")
      (footprint "TSOP65P210X110-6N")
      (description "IC SPDT,max 25R at VCC 4.5V tPD 1.2ns VCC 1.65V to 5V Iq max 10uA SOT363")
      (fields (field (name "MANUFACTURER") "ON Semiconductor"))
      (libsource (lib "Clean") (part "NLASB3157DFT2G-Symbol-1"))
    )
    (comp (ref "U3")
      (value "ISL854102FRZ-T")
      (footprint "QFN0P300X400X100_HS-13L")
      (description "IC BUCK Vin 40V Iout 1.2A 2MHz 12DFN 3x4mm")
      (fields (field (name "MANUFACTURER") "Renesas"))
      (libsource (lib "Clean") (part "ISL854102FRZ-T"))
    )
    (comp (ref "U4")
      (value "TXB0108DQSR")
      (footprint "FP-DQS0020A-MFG")
      (description "IC TRANSLATOR LEVEL SHIFTER BIDIR 8BIT 20SON")
      (fields (field (name "MANUFACTURER") "Texas Instruments"))
      (libsource (lib "Clean") (part "TXB0108DQSR"))
    )
    (comp (ref "U5")
      (value "SGM2205-3.3XKC3G/TR")
      (footprint "SOT223-3")
      (description "IC LINEAR REGULATOR Vout 3V3 fixed Vin max 20V Iout max 800mA Pd 1.32W")
      (fields (field (name "MANUFACTURER") "SGMICRO"))
      (libsource (lib "Clean") (part "SGM2205-3.3XKC3G_TR-Symbol-1"))
    )
    (comp (ref "U6")
      (value "NLASB3157DFT2G")
      (footprint "TSOP65P210X110-6N")
      (description "IC SPDT,max 25R at VCC 4.5V tPD 1.2ns VCC 1.65V to 5V Iq max 10uA SOT363")
      (fields (field (name "MANUFACTURER") "ON Semiconductor"))
      (libsource (lib "Clean") (part "NLASB3157DFT2G-Symbol-1"))
    )
    (comp (ref "uC_VBUS")
      (value "CMP-018-0004-A.4")
      (footprint "TP-0.8MM")
      (description "Test point 0.8mm")
      (libsource (lib "Clean") (part "TESTPOINT"))
    )
    (comp (ref "VBUS_CONN")
      (value "CMP-018-0005-A.3")
      (footprint "TP-1.00MM")
      (description "Test point 1.00mm")
      (libsource (lib "Clean") (part "TESTPOINT"))
    )
    (comp (ref "VCONN_TOP")
      (value "CMP-018-0004-A.4")
      (footprint "TP-0.8MM")
      (description "Test point 0.8mm")
      (libsource (lib "Clean") (part "TESTPOINT"))
    )
    (comp (ref "VIN_TOP")
      (value "CMP-018-0004-A.4")
      (footprint "TP-0.8MM")
      (description "Test point 0.8mm")
      (libsource (lib "Clean") (part "TESTPOINT"))
    )
  )
  (nets
    (net (code "1") (name "+3V3") (class "Default")
      (node (ref "3V3_TOP") (pin "X") (pinfunction "X_X") (pintype "passive"))
      (node (ref "C10") (pin "2") (pinfunction "2_2") (pintype "passive"))
      (node (ref "C11") (pin "2") (pinfunction "2_2") (pintype "passive"))
      (node (ref "C26") (pin "2") (pinfunction "2_2") (pintype "passive"))
      (node (ref "DL2") (pin "A") (pinfunction "A_A") (pintype "passive"))
      (node (ref "F1") (pin "2") (pinfunction "2_2") (pintype "passive"))
      (node (ref "JANALOG") (pin "4") (pinfunction "3V3_4") (pintype "passive"))
      (node (ref "M1") (pin "3") (pinfunction "3V3_3") (pintype "passive"))
      (node (ref "R26") (pin "1") (pinfunction "1_1") (pintype "passive"))
      (node (ref "R49") (pin "2") (pinfunction "2_2") (pintype "passive"))
      (node (ref "R56") (pin "2") (pinfunction "2_2") (pintype "passive"))
      (node (ref "R58") (pin "2") (pinfunction "2_2") (pintype "passive"))
      (node (ref "U4") (pin "5") (pinfunction "VCCA_5") (pintype "power_in"))
      (node (ref "U5") (pin "3") (pinfunction "OUT_(3V3)_3") (pintype "passive"))
    )
    (net (code "2") (name "+3V3_I2C") (class "Default")
      (node (ref "3V3_IC") (pin "X") (pinfunction "X_X") (pintype "passive"))
      (node (ref "F1") (pin "1") (pinfunction "1_1") (pintype "passive"))
      (node (ref "J2") (pin "2") (pinfunction "VCC_2") (pintype "passive"))
      (node (ref "Q1") (pin "1") (pinfunction "G_1") (pintype "passive"))
      (node (ref "Q2") (pin "1") (pinfunction "G_1") (pintype "passive"))
      (node (ref "R11") (pin "1") (pinfunction "1_1") (pintype "passive"))
      (node (ref "R9") (pin "1") (pinfunction "1_1") (pintype "passive"))
    )
    (net (code "3") (name "+5V") (class "Default")
      (node (ref "5V_TOP") (pin "X") (pinfunction "X_X") (pintype "passive"))
      (node (ref "C2") (pin "2") (pinfunction "2_2") (pintype "passive"))
      (node (ref "C24") (pin "2") (pinfunction "2_2") (pintype "passive"))
      (node (ref "C25") (pin "2") (pinfunction "2_2") (pintype "passive"))
      (node (ref "C28") (pin "2") (pinfunction "2_2") (pintype "passive"))
      (node (ref "C29") (pin "2") (pinfunction "2_2") (pintype "passive"))
      (node (ref "C3") (pin "2") (pinfunction "2_2") (pintype "passive"))
      (node (ref "C30") (pin "2") (pinfunction "2_2") (pintype "passive"))
      (node (ref "D2") (pin "C") (pinfunction "C_C") (pintype "passive"))
      (node (ref "DL1") (pin "A") (pinfunction "A_A") (pintype "passive"))
      (node (ref "DL3") (pin "A") (pinfunction "A_A") (pintype "passive"))
      (node (ref "DL4") (pin "A") (pinfunction "A_A") (pintype "passive"))
      (node (ref "J3") (pin "2") (pinfunction "2_2") (pintype "passive"))
      (node (ref "JANALOG") (pin "2") (pinfunction "IOREF_2") (pintype "passive"))
      (node (ref "JANALOG") (pin "5") (pinfunction "5V_5") (pintype "passive"))
      (node (ref "L2") (pin "1") (pinfunction "1_1") (pintype "passive"))
      (node (ref "R10") (pin "1") (pinfunction "1_1") (pintype "passive"))
      (node (ref "R12") (pin "1") (pinfunction "1_1") (pintype "passive"))
      (node (ref "R13") (pin "1") (pinfunction "1_1") (pintype "passive"))
      (node (ref "R3") (pin "2") (pinfunction "2_2") (pintype "passive"))
      (node (ref "R36") (pin "2") (pinfunction "2_2") (pintype "passive"))
      (node (ref "R4") (pin "2") (pinfunction "2_2") (pintype "passive"))
      (node (ref "R5") (pin "2") (pinfunction "2_2") (pintype "passive"))
      (node (ref "R59") (pin "2") (pinfunction "2_2") (pintype "passive"))
      (node (ref "R6") (pin "2") (pinfunction "2_2") (pintype "passive"))
      (node (ref "R7") (pin "1") (pinfunction "1_1") (pintype "passive"))
      (node (ref "R8") (pin "1") (pinfunction "1_1") (pintype "passive"))
      (node (ref "SJ1") (pin "1") (pinfunction "1_1") (pintype "passive"))
      (node (ref "U1") (pin "11") (pinfunction "VCC_11") (pintype "passive"))
      (node (ref "U1") (pin "21") (pinfunction "VCC_USB_LDO_21") (pintype "passive"))
      (node (ref "U1") (pin "39") (pinfunction "VCC_39") (pintype "passive"))
      (node (ref "U2") (pin "5") (pinfunction "VCC_5") (pintype "passive"))
      (node (ref "U4") (pin "16") (pinfunction "VCCB_16") (pintype "power_in"))
      (node (ref "U5") (pin "1") (pinfunction "IN_1") (pintype "passive"))
      (node (ref "U6") (pin "5") (pinfunction "VCC_5") (pintype "passive"))
    )
    (net (code "4") (name "/AREF") (class "Default")
      (node (ref "JDIGITAL") (pin "16") (pinfunction "AREF_16") (pintype "passive"))
      (node (ref "L1") (pin "1") (pinfunction "1_1") (pintype "passive"))
      (node (ref "R6") (pin "1") (pinfunction "1_1") (pintype "passive"))
    )
    (net (code "5") (name "/CC1") (class "Default")
      (node (ref "CC1") (pin "X") (pinfunction "X_X") (pintype "passive"))
      (node (ref "J1") (pin "A5") (pinfunction "CC1_A5") (pintype "passive"))
      (node (ref "R50") (pin "2") (pinfunction "2_2") (pintype "passive"))
    )
    (net (code "6") (name "/CC2") (class "Default")
      (node (ref "CC2") (pin "X") (pinfunction "X_X") (pintype "passive"))
      (node (ref "J1") (pin "B5") (pinfunction "CC2_B5") (pintype "passive"))
      (node (ref "R51") (pin "2") (pinfunction "2_2") (pintype "passive"))
    )
    (net (code "7") (name "/ESP32_ENABLE") (class "Default")
      (node (ref "ESP_EN_BOTTOM") (pin "X") (pinfunction "X_X") (pintype "passive"))
      (node (ref "ESP_EN_TOP") (pin "X") (pinfunction "X_X") (pintype "passive"))
      (node (ref "M1") (pin "45") (pinfunction "EN_45") (pintype "passive"))
      (node (ref "R26") (pin "2") (pinfunction "2_2") (pintype "passive"))
    )
    (net (code "8") (name "/ESP_DOWNLOAD") (class "Default")
      (node (ref "ESP_DOWNLOAD_BOTTOM1") (pin "X") (pinfunction "X_X") (pintype "passive"))
      (node (ref "ESP_DOWNLOAD_TOP") (pin "X") (pinfunction "X_X") (pintype "passive"))
      (node (ref "J6") (pin "4") (pinfunction "4_4") (pintype "passive"))
      (node (ref "M1") (pin "4") (pinfunction "BOOT_GPIO0_4") (pintype "passive"))
    )
    (net (code "9") (name "/ESP_IO1") (class "Default")
      (node (ref "ESP_IO1") (pin "X") (pinfunction "X_X") (pintype "passive"))
      (node (ref "M1") (pin "5") (pinfunction "ADC1CH0_GPIO1_5") (pintype "passive"))
    )
    (net (code "10") (name "/ESP_IO4") (class "Default")
      (node (ref "ESP_IO4") (pin "X") (pinfunction "X_X") (pintype "passive"))
      (node (ref "M1") (pin "8") (pinfunction "ADC1CH3_GPIO4_8") (pintype "passive"))
      (node (ref "R58") (pin "1") (pinfunction "1_1") (pintype "passive"))
      (node (ref "U4") (pin "1") (pinfunction "A1_1") (pintype "passive"))
    )
    (net (code "11") (name "/ESP_IO5") (class "Default")
      (node (ref "ESP_IO5") (pin "X") (pinfunction "X_X") (pintype "passive"))
      (node (ref "M1") (pin "9") (pinfunction "ADC1CH4_GPIO5_9") (pintype "passive"))
      (node (ref "U4") (pin "2") (pinfunction "A2_2") (pintype "passive"))
    )
    (net (code "12") (name "/ESP_IO6") (class "Default")
      (node (ref "ESP_IO6") (pin "X") (pinfunction "X_X") (pintype "passive"))
      (node (ref "M1") (pin "10") (pinfunction "ADC1CH5_GPIO6_10") (pintype "passive"))
      (node (ref "U4") (pin "3") (pinfunction "A3_3") (pintype "passive"))
    )
    (net (code "13") (name "/ESP_IO7") (class "Default")
      (node (ref "ESP_IO7") (pin "X") (pinfunction "X_X") (pintype "passive"))
      (node (ref "M1") (pin "11") (pinfunction "ADC1CH6_GPIO7_11") (pintype "passive"))
      (node (ref "U4") (pin "4") (pinfunction "A4_4") (pintype "passive"))
    )
    (net (code "14") (name "/ESP_IO8") (class "Default")
      (node (ref "ESP_IO8") (pin "X") (pinfunction "X_X") (pintype "passive"))
      (node (ref "M1") (pin "12") (pinfunction "ADC1CH7_GPIO8_12") (pintype "passive"))
      (node (ref "U4") (pin "7") (pinfunction "A5_7") (pintype "passive"))
    )
    (net (code "15") (name "/ESP_IO9") (class "Default")
      (node (ref "ESP_IO9") (pin "X") (pinfunction "X_X") (pintype "passive"))
      (node (ref "M1") (pin "13") (pinfunction "ADC1CH8_GPIO9_13") (pintype "passive"))
      (node (ref "U4") (pin "8") (pinfunction "A6_8") (pintype "passive"))
    )
    (net (code "16") (name "/ESP_IO41") (class "Default")
      (node (ref "ESP_MTDI") (pin "X") (pinfunction "X_X") (pintype "passive"))
      (node (ref "J6") (pin "2") (pinfunction "2_2") (pintype "passive"))
      (node (ref "M1") (pin "37") (pinfunction "MTDI_GPIO41_37") (pintype "passive"))
    )
    (net (code "17") (name "/ESP_IO42") (class "Default")
      (node (ref "ESP_MTMS") (pin "X") (pinfunction "X_X") (pintype "passive"))
      (node (ref "J6") (pin "1") (pinfunction "1_1") (pintype "passive"))
      (node (ref "M1") (pin "38") (pinfunction "MTMS_GPIO42_38") (pintype "passive"))
    )
    (net (code "18") (name "/ESP_MTCK") (class "Default")
      (node (ref "ESP_MTCK") (pin "X") (pinfunction "X_X") (pintype "passive"))
      (node (ref "M1") (pin "35") (pinfunction "MTCK_GPIO39_35") (pintype "passive"))
    )
    (net (code "19") (name "/ESP_MTDO") (class "Default")
      (node (ref "ESP_MTDO") (pin "X") (pinfunction "X_X") (pintype "passive"))
      (node (ref "M1") (pin "36") (pinfunction "MTDO_GPIO40_36") (pintype "passive"))
    )
    (net (code "20") (name "/ESP_N") (class "Default")
      (node (ref "D-_TOP") (pin "X") (pinfunction "X_X") (pintype "passive"))
      (node (ref "M1") (pin "23") (pinfunction "USBDN_ADC2CH8_GPIO19_23") (pintype "passive"))
      (node (ref "R53") (pin "1") (pinfunction "1_1") (pintype "passive"))
      (node (ref "U6") (pin "3") (pinfunction "B0_3") (pintype "passive"))
    )
    (net (code "21") (name "/ESP_P") (class "Default")
      (node (ref "D+_TOP") (pin "X") (pinfunction "X_X") (pintype "passive"))
      (node (ref "M1") (pin "24") (pinfunction "USBDP_ADC2CH9_GPIO20_24") (pintype "passive"))
      (node (ref "R21") (pin "1") (pinfunction "1_1") (pintype "passive"))
      (node (ref "U2") (pin "3") (pinfunction "B0_3") (pintype "passive"))
    )
    (net (code "22") (name "/ESP_RXD0") (class "Default")
      (node (ref "J6") (pin "5") (pinfunction "5_5") (pintype "passive"))
      (node (ref "R18") (pin "1") (pinfunction "1_1") (pintype "passive"))
      (node (ref "U4") (pin "10") (pinfunction "A8_10") (pintype "passive"))
    )
    (net (code "23") (name "/ESP_TXD0") (class "Default")
      (node (ref "J6") (pin "3") (pinfunction "3_3") (pintype "passive"))
      (node (ref "R17") (pin "1") (pinfunction "1_1") (pintype "passive"))
      (node (ref "R20") (pin "1") (pinfunction "1_1") (pintype "passive"))
      (node (ref "R23") (pin "1") (pinfunction "1_1") (pintype "passive"))
      (node (ref "U4") (pin "9") (pinfunction "A7_9") (pintype "passive"))
    )
    (net (code "24") (name "/EXT_SCL") (class "Default")
      (node (ref "EXT_SCL") (pin "X") (pinfunction "X_X") (pintype "passive"))
      (node (ref "J2") (pin "4") (pinfunction "SCL_4") (pintype "passive"))
      (node (ref "Q1") (pin "2") (pinfunction "S_2") (pintype "passive"))
      (node (ref "R9") (pin "2") (pinfunction "2_2") (pintype "passive"))
    )
    (net (code "25") (name "/EXT_SDA") (class "Default")
      (node (ref "EXT_SDA") (pin "X") (pinfunction "X_X") (pintype "passive"))
      (node (ref "J2") (pin "3") (pinfunction "SDA_3") (pintype "passive"))
      (node (ref "Q2") (pin "2") (pinfunction "S_2") (pintype "passive"))
      (node (ref "R11") (pin "2") (pinfunction "2_2") (pintype "passive"))
    )
    (net (code "26") (name "/ISL_VCC") (class "Default")
      (node (ref "C20") (pin "1") (pinfunction "1_1") (pintype "passive"))
      (node (ref "R37") (pin "2") (pinfunction "2_2") (pintype "passive"))
      (node (ref "R42") (pin "2") (pinfunction "2_2") (pintype "passive"))
      (node (ref "U3") (pin "1") (pinfunction "SS_1") (pintype "passive"))
      (node (ref "U3") (pin "9") (pinfunction "VCC_9") (pintype "power_in"))
    )
    (net (code "27") (name "/MD") (class "Default")
      (node (ref "JANALOG") (pin "1") (pinfunction "NC_1") (pintype "passive"))
      (node (ref "MD") (pin "X") (pinfunction "X_X") (pintype "passive"))
      (node (ref "R8") (pin "2") (pinfunction "2_2") (pintype "passive"))
      (node (ref "U1") (pin "26") (pinfunction "MD/P201_26") (pintype "passive"))
      (node (ref "U4") (pin "13") (pinfunction "B6_13") (pintype "passive"))
    )
    (net (code "28") (name "/OFF") (class "Default")
      (node (ref "JOFF") (pin "1") (pinfunction "1_1") (pintype "passive"))
      (node (ref "R35") (pin "2") (pinfunction "2_2") (pintype "passive"))
      (node (ref "U3") (pin "7") (pinfunction "EN_7") (pintype "passive"))
    )
    (net (code "29") (name "/P000_AN00_AMP+") (class "Default")
      (node (ref "JANALOG") (pin "10") (pinfunction "A1_10") (pintype "passive"))
      (node (ref "U1") (pin "64") (pinfunction "AN000/P000_64") (pintype "passive"))
    )
    (net (code "30") (name "/P001_AN01_AMP-") (class "Default")
      (node (ref "JANALOG") (pin "11") (pinfunction "A2_11") (pintype "passive"))
      (node (ref "U1") (pin "63") (pinfunction "AN001/P001_63") (pintype "passive"))
    )
    (net (code "31") (name "/P002_AN02_AMPO") (class "Default")
      (node (ref "JANALOG") (pin "12") (pinfunction "A3_12") (pintype "passive"))
      (node (ref "U1") (pin "62") (pinfunction "AN002/P002_62") (pintype "passive"))
    )
    (net (code "32") (name "/P003") (class "Default")
      (node (ref "U1") (pin "61") (pinfunction "AN003/P003_61") (pintype "passive"))
    )
    (net (code "33") (name "/P004") (class "Default")
      (node (ref "U1") (pin "60") (pinfunction "AN004/P004_60") (pintype "passive"))
    )
    (net (code "34") (name "/P011") (class "Default")
      (node (ref "U1") (pin "58") (pinfunction "VREFL0/AN006/P011_58") (pintype "passive"))
    )
    (net (code "35") (name "/P012") (class "Default")
      (node (ref "U1") (pin "55") (pinfunction "VREFH/AN007/P012_55") (pintype "passive"))
    )
    (net (code "36") (name "/P013") (class "Default")
      (node (ref "U1") (pin "54") (pinfunction "VREFL/AN008/P013_54") (pintype "passive"))
    )
    (net (code "37") (name "/P014_AN09_DAC") (class "Default")
      (node (ref "JANALOG") (pin "9") (pinfunction "A0_9") (pintype "passive"))
      (node (ref "U1") (pin "53") (pinfunction "DA0/AN009/P014_53") (pintype "passive"))
    )
    (net (code "38") (name "/P015") (class "Default")
      (node (ref "U1") (pin "52") (pinfunction "AN010/P015_52") (pintype "passive"))
    )
    (net (code "39") (name "/P100_AN22_SCL") (class "Default")
      (node (ref "JANALOG") (pin "14") (pinfunction "A5_14") (pintype "passive"))
      (node (ref "JDIGITAL") (pin "18") (pinfunction "SCL_18") (pintype "passive"))
      (node (ref "R4") (pin "1") (pinfunction "1_1") (pintype "passive"))
      (node (ref "U1") (pin "48") (pinfunction "GTIOC5B/AN022/P100_48") (pintype "passive"))
    )
    (net (code "40") (name "/P101_AN21_SDA") (class "Default")
      (node (ref "JANALOG") (pin "13") (pinfunction "A4_13") (pintype "passive"))
      (node (ref "JDIGITAL") (pin "17") (pinfunction "SDA_17") (pintype "passive"))
      (node (ref "R5") (pin "1") (pinfunction "1_1") (pintype "passive"))
      (node (ref "U1") (pin "47") (pinfunction "GTIOC5A/AN021/P101_47") (pintype "passive"))
    )
    (net (code "41") (name "/P102_SPI0_RSPCK_GPT2_B_CAN0_RX") (class "Default")
      (node (ref "J3") (pin "3") (pinfunction "3_3") (pintype "passive"))
      (node (ref "JDIGITAL") (pin "14") (pinfunction "D13/SCK_14") (pintype "passive"))
      (node (ref "Q3") (pin "1") (pinfunction "G_1") (pintype "passive"))
      (node (ref "R52") (pin "2") (pinfunction "2_2") (pintype "passive"))
      (node (ref "U1") (pin "46") (pinfunction "ADTRG0/GTIOC2B/AN020/P102_46") (pintype "passive"))
    )
    (net (code "42") (name "/P103_SPI0_SSL_GPT2_A_CAN0_TX") (class "Default")
      (node (ref "JDIGITAL") (pin "11") (pinfunction "D10/CS_11") (pintype "passive"))
      (node (ref "U1") (pin "45") (pinfunction "GTIOC2A/AN019/P103_45") (pintype "passive"))
    )
    (net (code "43") (name "/P104_IRQ01_GPT1_B") (class "Default")
      (node (ref "JDIGITAL") (pin "3") (pinfunction "D2_3") (pintype "passive"))
      (node (ref "U1") (pin "44") (pinfunction "GTIOC1B/P104_44") (pintype "passive"))
    )
    (net (code "44") (name "/P105_IRQ00_GPT1_A") (class "Default")
      (node (ref "JDIGITAL") (pin "4") (pinfunction "D3_4") (pintype "passive"))
      (node (ref "U1") (pin "43") (pinfunction "GTIOC1A/P105_43") (pintype "passive"))
    )
    (net (code "45") (name "/P106_GPT0_B") (class "Default")
      (node (ref "JDIGITAL") (pin "5") (pinfunction "D4_5") (pintype "passive"))
      (node (ref "U1") (pin "42") (pinfunction "GTIOC0B/P106_42") (pintype "passive"))
    )
    (net (code "46") (name "/P107_GPT0_A") (class "Default")
      (node (ref "JDIGITAL") (pin "6") (pinfunction "D5_6") (pintype "passive"))
      (node (ref "U1") (pin "41") (pinfunction "GTIOC0A/P107_41") (pintype "passive"))
    )
    (net (code "47") (name "/P108_SWDIO") (class "Default")
      (node (ref "SWDIO") (pin "X") (pinfunction "X_X") (pintype "passive"))
      (node (ref "U1") (pin "33") (pinfunction "P108/GTIOC0B/TMS/SWDIO_33") (pintype "passive"))
      (node (ref "U4") (pin "14") (pinfunction "B5_14") (pintype "passive"))
    )
    (net (code "48") (name "/P109_SCI9_TXD") (class "Default")
      (node (ref "R22") (pin "1") (pinfunction "1_1") (pintype "passive"))
      (node (ref "R48") (pin "1") (pinfunction "1_1") (pintype "passive"))
      (node (ref "U1") (pin "34") (pinfunction "CTX0/TDO/SWO/GTIOC1A/P109_34") (pintype "passive"))
    )
    (net (code "49") (name "/P110_SCI9_RXD") (class "Default")
      (node (ref "R47") (pin "1") (pinfunction "1_1") (pintype "passive"))
      (node (ref "U1") (pin "35") (pinfunction "CRX0/TDI/GTIOC1B/P110_35") (pintype "passive"))
    )
    (net (code "50") (name "/P111_GPT3_A") (class "Default")
      (node (ref "JDIGITAL") (pin "7") (pinfunction "D6_7") (pintype "passive"))
      (node (ref "U1") (pin "36") (pinfunction "GTIOC3A/P111_36") (pintype "passive"))
    )
    (net (code "51") (name "/P112_GPT3_B") (class "Default")
      (node (ref "JDIGITAL") (pin "8") (pinfunction "D7_8") (pintype "passive"))
      (node (ref "U1") (pin "37") (pinfunction "GTIOC3B/P112_37") (pintype "passive"))
    )
    (net (code "52") (name "/P204") (class "Default")
      (node (ref "U1") (pin "24") (pinfunction "GTIOC4B/P204_24") (pintype "passive"))
    )
    (net (code "53") (name "/P205") (class "Default")
      (node (ref "U1") (pin "23") (pinfunction "GTIOC4A/P205_23") (pintype "passive"))
    )
    (net (code "54") (name "/P206") (class "Default")
      (node (ref "U1") (pin "22") (pinfunction "P206_22") (pintype "passive"))
    )
    (net (code "55") (name "/P212") (class "Default")
      (node (ref "U1") (pin "10") (pinfunction "P212/GTIOC0B/EXTAL_10") (pintype "passive"))
    )
    (net (code "56") (name "/P213") (class "Default")
      (node (ref "U1") (pin "9") (pinfunction "P213/GTIOC0A/XTAL_9") (pintype "passive"))
    )
    (net (code "57") (name "/P300_SWCLK") (class "Default")
      (node (ref "SWCLK") (pin "X") (pinfunction "X_X") (pintype "passive"))
      (node (ref "U1") (pin "32") (pinfunction "P300/GTIOC0A/TCK/SWCLK_32") (pintype "passive"))
      (node (ref "U4") (pin "17") (pinfunction "B4_17") (pintype "passive"))
    )
    (net (code "58") (name "/P301_SCI2_RXD") (class "Default")
      (node (ref "JDIGITAL") (pin "1") (pinfunction "D0/RX_1") (pintype "passive"))
      (node (ref "U1") (pin "31") (pinfunction "GTIOC4B/P301_31") (pintype "passive"))
    )
    (net (code "59") (name "/P302_SCI2_TXD") (class "Default")
      (node (ref "JDIGITAL") (pin "2") (pinfunction "D1/TX_2") (pintype "passive"))
      (node (ref "U1") (pin "30") (pinfunction "GTIOC4A/P302_30") (pintype "passive"))
    )
    (net (code "60") (name "/P303_GPT7_B") (class "Default")
      (node (ref "JDIGITAL") (pin "10") (pinfunction "D9_10") (pintype "passive"))
      (node (ref "U1") (pin "29") (pinfunction "GTIOC7B/P303_29") (pintype "passive"))
    )
    (net (code "61") (name "/P304_GPT7_A") (class "Default")
      (node (ref "JDIGITAL") (pin "9") (pinfunction "D8_9") (pintype "passive"))
      (node (ref "U1") (pin "28") (pinfunction "GTIOC7A/P304_28") (pintype "passive"))
    )
    (net (code "62") (name "/P400_IIC0_SCL") (class "Default")
      (node (ref "P400_SCL") (pin "X") (pinfunction "X_X") (pintype "passive"))
      (node (ref "Q1") (pin "3") (pinfunction "D_3") (pintype "passive"))
      (node (ref "R10") (pin "2") (pinfunction "2_2") (pintype "passive"))
      (node (ref "U1") (pin "1") (pinfunction "P400/GTIOC6A_1") (pintype "passive"))
    )
    (net (code "63") (name "/P401_IIC0_SDA") (class "Default")
      (node (ref "P401_SDA") (pin "X") (pinfunction "X_X") (pintype "passive"))
      (node (ref "Q2") (pin "3") (pinfunction "D_3") (pintype "passive"))
      (node (ref "R12") (pin "2") (pinfunction "2_2") (pintype "passive"))
      (node (ref "U1") (pin "2") (pinfunction "P401/GTIOC6B/CTX0_2") (pintype "passive"))
    )
    (net (code "64") (name "/P408") (class "Default")
      (node (ref "R1") (pin "2") (pinfunction "2_2") (pintype "passive"))
      (node (ref "SJ1") (pin "2") (pinfunction "2_2") (pintype "passive"))
      (node (ref "U1") (pin "15") (pinfunction "P408/GTIOC5B/USB_ID_15") (pintype "passive"))
      (node (ref "U2") (pin "6") (pinfunction "SELECT_6") (pintype "passive"))
      (node (ref "U6") (pin "6") (pinfunction "SELECT_6") (pintype "passive"))
    )
    (net (code "65") (name "/P410_SPI0_MISO_GPT6_B") (class "Default")
      (node (ref "J3") (pin "1") (pinfunction "1_1") (pintype "passive"))
      (node (ref "JDIGITAL") (pin "13") (pinfunction "D12/MISO_13") (pintype "passive"))
      (node (ref "U1") (pin "13") (pinfunction "P410/GTIOC6B_13") (pintype "passive"))
    )
    (net (code "66") (name "/P411_SPI0_MOSI_GPT6_A") (class "Default")
      (node (ref "J3") (pin "4") (pinfunction "4_4") (pintype "passive"))
      (node (ref "JDIGITAL") (pin "12") (pinfunction "D11/MOSI_12") (pintype "passive"))
      (node (ref "U1") (pin "12") (pinfunction "P411/GTIOC6A_12") (pintype "passive"))
    )
    (net (code "67") (name "/P501_SCI1_TXD") (class "Default")
      (node (ref "R45") (pin "1") (pinfunction "1_1") (pintype "passive"))
      (node (ref "U1") (pin "50") (pinfunction "GTIOC2B/AN017/P501_50") (pintype "passive"))
    )
    (net (code "68") (name "/P502_SCI1_RXD") (class "Default")
      (node (ref "R46") (pin "1") (pinfunction "1_1") (pintype "passive"))
      (node (ref "U1") (pin "51") (pinfunction "GTIOC3B/AN018/P502_51") (pintype "passive"))
    )
    (net (code "69") (name "/RA4_N") (class "Default")
      (node (ref "R55") (pin "1") (pinfunction "1_1") (pintype "passive"))
      (node (ref "U1") (pin "18") (pinfunction "P915/USB_DM_18") (pintype "passive"))
      (node (ref "U6") (pin "1") (pinfunction "B1_1") (pintype "passive"))
    )
    (net (code "70") (name "/RA4_P") (class "Default")
      (node (ref "R54") (pin "1") (pinfunction "1_1") (pintype "passive"))
      (node (ref "U1") (pin "19") (pinfunction "P914/USB_DP_19") (pintype "passive"))
      (node (ref "U2") (pin "1") (pinfunction "B1_1") (pintype "passive"))
    )
    (net (code "71") (name "/SHIELD1") (class "Default")
      (node (ref "C21") (pin "2") (pinfunction "2_2") (pintype "passive"))
      (node (ref "D3") (pin "1") (pinfunction "1_1") (pintype "passive"))
      (node (ref "J1") (pin "SHIELD1") (pinfunction "SHIELD1_SHIELD1") (pintype "passive"))
      (node (ref "R39") (pin "2") (pinfunction "2_2") (pintype "passive"))
    )
    (net (code "72") (name "/USB_D_N") (class "Default")
      (node (ref "D-") (pin "X") (pinfunction "X_X") (pintype "passive"))
      (node (ref "D3") (pin "3") (pinfunction "3_3") (pintype "passive"))
      (node (ref "J1") (pin "A7") (pinfunction "D-_A7") (pintype "passive"))
      (node (ref "J1") (pin "B7") (pinfunction "D-_B7") (pintype "passive"))
      (node (ref "R53") (pin "2") (pinfunction "2_2") (pintype "passive"))
      (node (ref "R55") (pin "2") (pinfunction "2_2") (pintype "passive"))
      (node (ref "U6") (pin "4") (pinfunction "A_4") (pintype "passive"))
    )
    (net (code "73") (name "/USB_D_P") (class "Default")
      (node (ref "D+") (pin "X") (pinfunction "X_X") (pintype "passive"))
      (node (ref "D3") (pin "2") (pinfunction "2_2") (pintype "passive"))
      (node (ref "J1") (pin "A6") (pinfunction "D+_A6") (pintype "passive"))
      (node (ref "J1") (pin "B6") (pinfunction "D+_B6") (pintype "passive"))
      (node (ref "R21") (pin "2") (pinfunction "2_2") (pintype "passive"))
      (node (ref "R54") (pin "2") (pinfunction "2_2") (pintype "passive"))
      (node (ref "U2") (pin "4") (pinfunction "A_4") (pintype "passive"))
    )
    (net (code "74") (name "/VBATT") (class "Default")
      (node (ref "C8") (pin "2") (pinfunction "2_2") (pintype "passive"))
      (node (ref "JOFF") (pin "3") (pinfunction "3_3") (pintype "passive"))
      (node (ref "U1") (pin "4") (pinfunction "VBATT_4") (pintype "passive"))
    )
    (net (code "75") (name "/VREFH0") (class "Default")
      (node (ref "C7") (pin "2") (pinfunction "2_2") (pintype "passive"))
      (node (ref "L1") (pin "2") (pinfunction "2_2") (pintype "passive"))
      (node (ref "U1") (pin "59") (pinfunction "P010/AN005/VREFH0_59") (pintype "passive"))
    )
    (net (code "76") (name "/~{RESET}") (class "Default")
      (node (ref "C1") (pin "1") (pinfunction "1_1") (pintype "passive"))
      (node (ref "J3") (pin "5") (pinfunction "5_5") (pintype "passive"))
      (node (ref "JANALOG") (pin "3") (pinfunction "RESET_3") (pintype "passive"))
      (node (ref "PB1") (pin "3") (pinfunction "3_3") (pintype "passive"))
      (node (ref "PB1") (pin "4") (pinfunction "4_4") (pintype "passive"))
      (node (ref "R3") (pin "1") (pinfunction "1_1") (pintype "passive"))
      (node (ref "RES") (pin "X") (pinfunction "X_X") (pintype "passive"))
      (node (ref "U1") (pin "25") (pinfunction "~{RES}_25") (pintype "passive"))
      (node (ref "U4") (pin "20") (pinfunction "B1_20") (pintype "passive"))
    )
    (net (code "77") (name "GND") (class "Default")
      (node (ref "C1") (pin "2") (pinfunction "2_2") (pintype "passive"))
      (node (ref "C10") (pin "1") (pinfunction "1_1") (pintype "passive"))
      (node (ref "C11") (pin "1") (pinfunction "1_1") (pintype "passive"))
      (node (ref "C15") (pin "1") (pinfunction "1_1") (pintype "passive"))
      (node (ref "C16") (pin "1") (pinfunction "1_1") (pintype "passive"))
      (node (ref "C17") (pin "1") (pinfunction "1_1") (pintype "passive"))
      (node (ref "C18") (pin "1") (pinfunction "1_1") (pintype "passive"))
      (node (ref "C19") (pin "1") (pinfunction "1_1") (pintype "passive"))
      (node (ref "C2") (pin "1") (pinfunction "1_1") (pintype "passive"))
      (node (ref "C20") (pin "2") (pinfunction "2_2") (pintype "passive"))
      (node (ref "C21") (pin "1") (pinfunction "1_1") (pintype "passive"))
      (node (ref "C22") (pin "1") (pinfunction "1_1") (pintype "passive"))
      (node (ref "C23") (pin "1") (pinfunction "1_1") (pintype "passive"))
      (node (ref "C24") (pin "1") (pinfunction "1_1") (pintype "passive"))
      (node (ref "C25") (pin "1") (pinfunction "1_1") (pintype "passive"))
      (node (ref "C26") (pin "1") (pinfunction "1_1") (pintype "passive"))
      (node (ref "C28") (pin "1") (pinfunction "1_1") (pintype "passive"))
      (node (ref "C29") (pin "1") (pinfunction "1_1") (pintype "passive"))
      (node (ref "C3") (pin "1") (pinfunction "1_1") (pintype "passive"))
      (node (ref "C30") (pin "1") (pinfunction "1_1") (pintype "passive"))
      (node (ref "C5") (pin "1") (pinfunction "1_1") (pintype "passive"))
      (node (ref "C6") (pin "2") (pinfunction "2_2") (pintype "passive"))
      (node (ref "C7") (pin "1") (pinfunction "1_1") (pintype "passive"))
      (node (ref "C8") (pin "1") (pinfunction "1_1") (pintype "passive"))
      (node (ref "C9") (pin "1") (pinfunction "1_1") (pintype "passive"))
      (node (ref "GND") (pin "X") (pinfunction "X_X") (pintype "passive"))
      (node (ref "GND2") (pin "X") (pinfunction "X_X") (pintype "passive"))
      (node (ref "J1") (pin "A1") (pinfunction "GND_A1") (pintype "passive"))
      (node (ref "J1") (pin "A12") (pinfunction "GND_A12") (pintype "passive"))
      (node (ref "J1") (pin "B1") (pinfunction "GND_B1") (pintype "passive"))
      (node (ref "J1") (pin "B12") (pinfunction "GND_B12") (pintype "passive"))
      (node (ref "J2") (pin "1") (pinfunction "GND_1") (pintype "passive"))
      (node (ref "J2") (pin "FIX") (pinfunction "FIX_FIX") (pintype "passive"))
      (node (ref "J3") (pin "6") (pinfunction "6_6") (pintype "passive"))
      (node (ref "J5") (pin "2") (pinfunction "2_2") (pintype "power_in"))
      (node (ref "J5") (pin "3") (pinfunction "3_3") (pintype "power_in"))
      (node (ref "J6") (pin "6") (pinfunction "6_6") (pintype "passive"))
      (node (ref "JANALOG") (pin "6") (pinfunction "GND_6") (pintype "passive"))
      (node (ref "JANALOG") (pin "7") (pinfunction "GND_7") (pintype "passive"))
      (node (ref "JDIGITAL") (pin "15") (pinfunction "GND_15") (pintype "passive"))
      (node (ref "JOFF") (pin "2") (pinfunction "2_2") (pintype "passive"))
      (node (ref "M1") (pin "1") (pinfunction "GND_1") (pintype "passive"))
      (node (ref "M1") (pin "2") (pinfunction "GND_2") (pintype "passive"))
      (node (ref "M1") (pin "42") (pinfunction "GND_42") (pintype "passive"))
      (node (ref "M1") (pin "43") (pinfunction "GND_43") (pintype "passive"))
      (node (ref "M1") (pin "46") (pinfunction "GND_46") (pintype "passive"))
      (node (ref "M1") (pin "47") (pinfunction "GND_47") (pintype "passive"))
      (node (ref "M1") (pin "48") (pinfunction "GND_48") (pintype "passive"))
      (node (ref "M1") (pin "49") (pinfunction "GND_49") (pintype "passive"))
      (node (ref "M1") (pin "50") (pinfunction "GND_50") (pintype "passive"))
      (node (ref "M1") (pin "51") (pinfunction "GND_51") (pintype "passive"))
      (node (ref "M1") (pin "52") (pinfunction "GND_52") (pintype "passive"))
      (node (ref "M1") (pin "53") (pinfunction "GND_53") (pintype "passive"))
      (node (ref "M1") (pin "54") (pinfunction "GND_54") (pintype "passive"))
      (node (ref "M1") (pin "55") (pinfunction "GND_55") (pintype "passive"))
      (node (ref "M1") (pin "56") (pinfunction "GND_56") (pintype "passive"))
      (node (ref "M1") (pin "57") (pinfunction "GND_57") (pintype "passive"))
      (node (ref "M1") (pin "58") (pinfunction "GND_58") (pintype "passive"))
      (node (ref "M1") (pin "59") (pinfunction "GND_59") (pintype "passive"))
      (node (ref "M1") (pin "60") (pinfunction "GND_60") (pintype "passive"))
      (node (ref "M1") (pin "61") (pinfunction "GND_61") (pintype "passive"))
      (node (ref "M1") (pin "62") (pinfunction "GND_62") (pintype "passive"))
      (node (ref "M1") (pin "63") (pinfunction "GND_63") (pintype "passive"))
      (node (ref "M1") (pin "64") (pinfunction "GND_64") (pintype "passive"))
      (node (ref "M1") (pin "65") (pinfunction "GND_65") (pintype "passive"))
      (node (ref "PB1") (pin "1") (pinfunction "1_1") (pintype "passive"))
      (node (ref "PB1") (pin "2") (pinfunction "2_2") (pintype "passive"))
      (node (ref "PB1") (pin "5") (pinfunction "5-GND_5") (pintype "power_in"))
      (node (ref "Q3") (pin "2") (pinfunction "S_2") (pintype "passive"))
      (node (ref "R1") (pin "1") (pinfunction "1_1") (pintype "passive"))
      (node (ref "R19") (pin "2") (pinfunction "2_2") (pintype "passive"))
      (node (ref "R24") (pin "1") (pinfunction "1_1") (pintype "passive"))
      (node (ref "R39") (pin "1") (pinfunction "1_1") (pintype "passive"))
      (node (ref "R40") (pin "1") (pinfunction "1_1") (pintype "passive"))
      (node (ref "R43") (pin "1") (pinfunction "1_1") (pintype "passive"))
      (node (ref "R44") (pin "1") (pinfunction "1_1") (pintype "passive"))
      (node (ref "R50") (pin "1") (pinfunction "1_1") (pintype "passive"))
      (node (ref "R51") (pin "1") (pinfunction "1_1") (pintype "passive"))
      (node (ref "R52") (pin "1") (pinfunction "1_1") (pintype "passive"))
      (node (ref "R57") (pin "1") (pinfunction "1_1") (pintype "passive"))
      (node (ref "R60") (pin "1") (pinfunction "1_1") (pintype "passive"))
      (node (ref "U1") (pin "17") (pinfunction "VSS_USB_17") (pintype "passive"))
      (node (ref "U1") (pin "40") (pinfunction "VSS_40") (pintype "passive"))
      (node (ref "U1") (pin "57") (pinfunction "AVSS0_57") (pintype "passive"))
      (node (ref "U1") (pin "8") (pinfunction "VSS_8") (pintype "passive"))
      (node (ref "U2") (pin "2") (pinfunction "GND_2") (pintype "passive"))
      (node (ref "U3") (pin "13") (pinfunction "GNDPAD_13") (pintype "power_in"))
      (node (ref "U3") (pin "6") (pinfunction "PGND_6") (pintype "power_in"))
      (node (ref "U4") (pin "15") (pinfunction "GND_15") (pintype "power_in"))
      (node (ref "U5") (pin "2") (pinfunction "GND_2") (pintype "passive"))
      (node (ref "U5") (pin "4") (pinfunction "GND_4") (pintype "passive"))
      (node (ref "U6") (pin "2") (pinfunction "GND_2") (pintype "passive"))
    )
    (net (code "78") (name "Net-(C13-Pad1)") (class "Default")
      (node (ref "C13") (pin "1") (pinfunction "1_1") (pintype "passive"))
      (node (ref "C19") (pin "2") (pinfunction "2_2") (pintype "passive"))
    )
    (net (code "79") (name "Net-(C14-Pad2)") (class "Default")
      (node (ref "C14") (pin "2") (pinfunction "2_2") (pintype "passive"))
      (node (ref "C15") (pin "2") (pinfunction "2_2") (pintype "passive"))
      (node (ref "C16") (pin "2") (pinfunction "2_2") (pintype "passive"))
      (node (ref "C17") (pin "2") (pinfunction "2_2") (pintype "passive"))
      (node (ref "C18") (pin "2") (pinfunction "2_2") (pintype "passive"))
      (node (ref "L3") (pin "2") (pinfunction "2_2") (pintype "passive"))
      (node (ref "R36") (pin "1") (pinfunction "1_1") (pintype "passive"))
      (node (ref "R38") (pin "1") (pinfunction "1_1") (pintype "passive"))
    )
    (net (code "80") (name "Net-(C22-Pad2)") (class "Default")
      (node (ref "C22") (pin "2") (pinfunction "2_2") (pintype "passive"))
      (node (ref "R41") (pin "1") (pinfunction "1_1") (pintype "passive"))
    )
    (net (code "81") (name "Net-(DL1-PadC)") (class "Default")
      (node (ref "DL1") (pin "C") (pinfunction "C_C") (pintype "passive"))
      (node (ref "R22") (pin "2") (pinfunction "2_2") (pintype "passive"))
    )
    (net (code "82") (name "Net-(DL2-PadC)") (class "Default")
      (node (ref "DL2") (pin "C") (pinfunction "C_C") (pintype "passive"))
      (node (ref "R20") (pin "2") (pinfunction "2_2") (pintype "passive"))
      (node (ref "R23") (pin "2") (pinfunction "2_2") (pintype "passive"))
    )
    (net (code "83") (name "Net-(DL3-PadC)") (class "Default")
      (node (ref "DL3") (pin "C") (pinfunction "C_C") (pintype "passive"))
      (node (ref "R24") (pin "2") (pinfunction "2_2") (pintype "passive"))
    )
    (net (code "84") (name "Net-(DL4-PadC)") (class "Default")
      (node (ref "DL4") (pin "C") (pinfunction "C_C") (pintype "passive"))
      (node (ref "R25") (pin "2") (pinfunction "2_2") (pintype "passive"))
    )
    (net (code "85") (name "Net-(M1-ADC1CH2_GPIO3)") (class "Default")
      (node (ref "M1") (pin "7") (pinfunction "ADC1CH2_GPIO3_7") (pintype "passive"))
      (node (ref "R56") (pin "1") (pinfunction "1_1") (pintype "passive"))
      (node (ref "R57") (pin "2") (pinfunction "2_2") (pintype "passive"))
    )
    (net (code "86") (name "Net-(M1-U0RXD{slash}GPIO44)") (class "Default")
      (node (ref "M1") (pin "40") (pinfunction "U0RXD/GPIO44_40") (pintype "passive"))
      (node (ref "R18") (pin "2") (pinfunction "2_2") (pintype "passive"))
    )
    (net (code "87") (name "Net-(M1-U0TXD{slash}GPIO43)") (class "Default")
      (node (ref "M1") (pin "39") (pinfunction "U0TXD/GPIO43_39") (pintype "passive"))
      (node (ref "R17") (pin "2") (pinfunction "2_2") (pintype "passive"))
    )
    (net (code "88") (name "Net-(Q3-D)") (class "Default")
      (node (ref "Q3") (pin "3") (pinfunction "D_3") (pintype "passive"))
      (node (ref "R25") (pin "1") (pinfunction "1_1") (pintype "passive"))
    )
    (net (code "89") (name "Net-(R15-Pad1)") (class "Default")
      (node (ref "R15") (pin "1") (pinfunction "1_1") (pintype "passive"))
      (node (ref "R19") (pin "1") (pinfunction "1_1") (pintype "passive"))
    )
    (net (code "90") (name "Net-(U1-AVCC0)") (class "Default")
      (node (ref "C6") (pin "1") (pinfunction "1_1") (pintype "passive"))
      (node (ref "L2") (pin "2") (pinfunction "2_2") (pintype "passive"))
      (node (ref "U1") (pin "56") (pinfunction "AVCC0_56") (pintype "passive"))
    )
    (net (code "91") (name "Net-(U1-GTIOC2A{slash}AN016{slash}P500)") (class "Default")
      (node (ref "R59") (pin "1") (pinfunction "1_1") (pintype "passive"))
      (node (ref "R60") (pin "2") (pinfunction "2_2") (pintype "passive"))
      (node (ref "U1") (pin "49") (pinfunction "GTIOC2A/AN016/P500_49") (pintype "passive"))
    )
    (net (code "92") (name "Net-(U1-GTIOC2A{slash}P113)") (class "Default")
      (node (ref "LOVE") (pin "X") (pinfunction "X_X") (pintype "passive"))
      (node (ref "U1") (pin "38") (pinfunction "GTIOC2A/P113_38") (pintype "passive"))
    )
    (net (code "93") (name "Net-(U1-NMI{slash}INPUT_ONLY_P200)") (class "Default")
      (node (ref "R7") (pin "2") (pinfunction "2_2") (pintype "passive"))
      (node (ref "U1") (pin "27") (pinfunction "NMI/INPUT_ONLY_P200_27") (pintype "passive"))
    )
    (net (code "94") (name "Net-(U1-P407{slash}USB_VBUS{slash}ADTRG0)") (class "Default")
      (node (ref "R13") (pin "2") (pinfunction "2_2") (pintype "passive"))
      (node (ref "R15") (pin "2") (pinfunction "2_2") (pintype "passive"))
      (node (ref "U1") (pin "16") (pinfunction "P407/USB_VBUS/ADTRG0_16") (pintype "passive"))
      (node (ref "uC_VBUS") (pin "X") (pinfunction "X_X") (pintype "passive"))
    )
    (net (code "95") (name "Net-(U1-VCC_USB)") (class "Default")
      (node (ref "C5") (pin "2") (pinfunction "2_2") (pintype "passive"))
      (node (ref "U1") (pin "20") (pinfunction "VCC_USB_20") (pintype "passive"))
    )
    (net (code "96") (name "Net-(U1-VCL)") (class "Default")
      (node (ref "C9") (pin "2") (pinfunction "2_2") (pintype "passive"))
      (node (ref "U1") (pin "5") (pinfunction "VCL_5") (pintype "passive"))
    )
    (net (code "97") (name "Net-(U3-BOOT)") (class "Default")
      (node (ref "C12") (pin "2") (pinfunction "2_2") (pintype "passive"))
      (node (ref "U3") (pin "3") (pinfunction "BOOT_3") (pintype "passive"))
    )
    (net (code "98") (name "Net-(U3-COMP)") (class "Default")
      (node (ref "C23") (pin "2") (pinfunction "2_2") (pintype "passive"))
      (node (ref "R41") (pin "2") (pinfunction "2_2") (pintype "passive"))
      (node (ref "R42") (pin "1") (pinfunction "1_1") (pintype "passive"))
      (node (ref "U3") (pin "11") (pinfunction "COMP_11") (pintype "passive"))
    )
    (net (code "99") (name "Net-(U3-FB)") (class "Default")
      (node (ref "C14") (pin "1") (pinfunction "1_1") (pintype "passive"))
      (node (ref "R38") (pin "2") (pinfunction "2_2") (pintype "passive"))
      (node (ref "R40") (pin "2") (pinfunction "2_2") (pintype "passive"))
      (node (ref "U3") (pin "10") (pinfunction "FB_10") (pintype "passive"))
    )
    (net (code "100") (name "Net-(U3-FS)") (class "Default")
      (node (ref "R43") (pin "2") (pinfunction "2_2") (pintype "passive"))
      (node (ref "R44") (pin "2") (pinfunction "2_2") (pintype "passive"))
      (node (ref "U3") (pin "12") (pinfunction "FS_12") (pintype "passive"))
    )
    (net (code "101") (name "Net-(U3-PHASE)") (class "Default")
      (node (ref "C12") (pin "1") (pinfunction "1_1") (pintype "passive"))
      (node (ref "L3") (pin "1") (pinfunction "1_1") (pintype "passive"))
      (node (ref "U3") (pin "5") (pinfunction "PHASE_5") (pintype "passive"))
    )
    (net (code "102") (name "Net-(U3-SYNC)") (class "Default")
      (node (ref "R37") (pin "1") (pinfunction "1_1") (pintype "passive"))
      (node (ref "U3") (pin "2") (pinfunction "SYNC_2") (pintype "passive"))
    )
    (net (code "103") (name "Net-(U3-VIN)") (class "Default")
      (node (ref "BUCK_IN_TOP") (pin "X") (pinfunction "X_X") (pintype "passive"))
      (node (ref "C13") (pin "2") (pinfunction "2_2") (pintype "passive"))
      (node (ref "D1") (pin "C") (pinfunction "C_C") (pintype "passive"))
      (node (ref "R35") (pin "1") (pinfunction "1_1") (pintype "passive"))
      (node (ref "U3") (pin "4") (pinfunction "VIN_4") (pintype "power_in"))
    )
    (net (code "104") (name "Net-(U4-B2)") (class "Default")
      (node (ref "R46") (pin "2") (pinfunction "2_2") (pintype "passive"))
      (node (ref "U4") (pin "19") (pinfunction "B2_19") (pintype "passive"))
    )
    (net (code "105") (name "Net-(U4-B3)") (class "Default")
      (node (ref "R45") (pin "2") (pinfunction "2_2") (pintype "passive"))
      (node (ref "U4") (pin "18") (pinfunction "B3_18") (pintype "passive"))
    )
    (net (code "106") (name "Net-(U4-B7)") (class "Default")
      (node (ref "R47") (pin "2") (pinfunction "2_2") (pintype "passive"))
      (node (ref "U4") (pin "12") (pinfunction "B7_12") (pintype "passive"))
    )
    (net (code "107") (name "Net-(U4-B8)") (class "Default")
      (node (ref "R48") (pin "2") (pinfunction "2_2") (pintype "passive"))
      (node (ref "U4") (pin "11") (pinfunction "B8_11") (pintype "passive"))
    )
    (net (code "108") (name "Net-(U4-OE)") (class "Default")
      (node (ref "R49") (pin "1") (pinfunction "1_1") (pintype "passive"))
      (node (ref "U4") (pin "6") (pinfunction "OE_6") (pintype "passive"))
    )
    (net (code "109") (name "VIN") (class "Default")
      (node (ref "D1") (pin "A") (pinfunction "A_A") (pintype "passive"))
      (node (ref "J5") (pin "1") (pinfunction "1_1") (pintype "power_in"))
      (node (ref "JANALOG") (pin "8") (pinfunction "VIN_8") (pintype "passive"))
      (node (ref "VIN_TOP") (pin "X") (pinfunction "X_X") (pintype "passive"))
    )
    (net (code "110") (name "VUSB") (class "Default")
      (node (ref "D2") (pin "A") (pinfunction "A_A") (pintype "passive"))
      (node (ref "D3") (pin "4") (pinfunction "4_4") (pintype "passive"))
      (node (ref "J1") (pin "A4") (pinfunction "VBUS_A4") (pintype "passive"))
      (node (ref "J1") (pin "A9") (pinfunction "VBUS_A9") (pintype "passive"))
      (node (ref "J1") (pin "B4") (pinfunction "VBUS_B4") (pintype "passive"))
      (node (ref "J1") (pin "B9") (pinfunction "VBUS_B9") (pintype "passive"))
      (node (ref "VBUS_CONN") (pin "X") (pinfunction "X_X") (pintype "passive"))
      (node (ref "VCONN_TOP") (pin "X") (pinfunction "X_X") (pintype "passive"))
    )
    (net (code "111") (name "unconnected-(Fiducial_1-Pad1)") (class "Default")
      (node (ref "Fiducial_1") (pin "1") (pinfunction "1_1") (pintype "passive+no_connect"))
    )
    (net (code "112") (name "unconnected-(Fiducial_2-Pad1)") (class "Default")
      (node (ref "Fiducial_2") (pin "1") (pinfunction "1_1") (pintype "passive+no_connect"))
    )
    (net (code "113") (name "unconnected-(J1-PadFIXING)") (class "Default")
      (node (ref "J1") (pin "FIXING") (pinfunction "FIXING_FIXING") (pintype "passive+no_connect"))
    )
    (net (code "114") (name "unconnected-(J1-PadSHIELD2)") (class "Default")
      (node (ref "J1") (pin "SHIELD2") (pinfunction "SHIELD2_SHIELD2") (pintype "passive+no_connect"))
    )
    (net (code "115") (name "unconnected-(J1-PadSHIELD3)") (class "Default")
      (node (ref "J1") (pin "SHIELD3") (pinfunction "SHIELD3_SHIELD3") (pintype "passive+no_connect"))
    )
    (net (code "116") (name "unconnected-(J1-PadSHIELD4)") (class "Default")
      (node (ref "J1") (pin "SHIELD4") (pinfunction "SHIELD4_SHIELD4") (pintype "passive+no_connect"))
    )
    (net (code "117") (name "unconnected-(J1-SBU1-PadA8)") (class "Default")
      (node (ref "J1") (pin "A8") (pinfunction "SBU1_A8") (pintype "passive+no_connect"))
    )
    (net (code "118") (name "unconnected-(J1-SBU2-PadB8)") (class "Default")
      (node (ref "J1") (pin "B8") (pinfunction "SBU2_B8") (pintype "passive+no_connect"))
    )
    (net (code "119") (name "unconnected-(M1-ADC1CH1_GPIO2-Pad6)") (class "Default")
      (node (ref "M1") (pin "6") (pinfunction "ADC1CH1_GPIO2_6") (pintype "passive+no_connect"))
    )
    (net (code "120") (name "unconnected-(M1-FSPICLK_GPIO36-Pad32)") (class "Default")
      (node (ref "M1") (pin "32") (pinfunction "FSPICLK_GPIO36_32") (pintype "passive+no_connect"))
    )
    (net (code "121") (name "unconnected-(M1-FSPICS0_GPIO34-Pad29)") (class "Default")
      (node (ref "M1") (pin "29") (pinfunction "FSPICS0_GPIO34_29") (pintype "passive+no_connect"))
    )
    (net (code "122") (name "unconnected-(M1-FSPIDQS_ADC2CH3_GPIO14-Pad18)") (class "Default")
      (node (ref "M1") (pin "18") (pinfunction "FSPIDQS_ADC2CH3_GPIO14_18") (pintype "passive+no_connect"))
    )
    (net (code "123") (name "unconnected-(M1-FSPID_GPIO35-Pad31)") (class "Default")
      (node (ref "M1") (pin "31") (pinfunction "FSPID_GPIO35_31") (pintype "passive+no_connect"))
    )
    (net (code "124") (name "unconnected-(M1-FSPIHD_GPIO33-Pad28)") (class "Default")
      (node (ref "M1") (pin "28") (pinfunction "FSPIHD_GPIO33_28") (pintype "passive+no_connect"))
    )
    (net (code "125") (name "unconnected-(M1-FSPII04_ADC1CH9_GPIO10-Pad14)") (class "Default")
      (node (ref "M1") (pin "14") (pinfunction "FSPII04_ADC1CH9_GPIO10_14") (pintype "passive+no_connect"))
    )
    (net (code "126") (name "unconnected-(M1-FSPIIO5_ADC2CH0_GPIO11-Pad15)") (class "Default")
      (node (ref "M1") (pin "15") (pinfunction "FSPIIO5_ADC2CH0_GPIO11_15") (pintype "passive+no_connect"))
    )
    (net (code "127") (name "unconnected-(M1-FSPIIO6_ADC2CH1_GPIO12-Pad16)") (class "Default")
      (node (ref "M1") (pin "16") (pinfunction "FSPIIO6_ADC2CH1_GPIO12_16") (pintype "passive+no_connect"))
    )
    (net (code "128") (name "unconnected-(M1-FSPIIO7_ADC2CH2_GPIO13-Pad17)") (class "Default")
      (node (ref "M1") (pin "17") (pinfunction "FSPIIO7_ADC2CH2_GPIO13_17") (pintype "passive+no_connect"))
    )
    (net (code "129") (name "unconnected-(M1-FSPIQ_GPIO37-Pad33)") (class "Default")
      (node (ref "M1") (pin "33") (pinfunction "FSPIQ_GPIO37_33") (pintype "passive+no_connect"))
    )
    (net (code "130") (name "unconnected-(M1-FSPIWP_GPIO38-Pad34)") (class "Default")
      (node (ref "M1") (pin "34") (pinfunction "FSPIWP_GPIO38_34") (pintype "passive+no_connect"))
    )
    (net (code "131") (name "unconnected-(M1-GPIO21-Pad25)") (class "Default")
      (node (ref "M1") (pin "25") (pinfunction "GPIO21_25") (pintype "passive+no_connect"))
    )
    (net (code "132") (name "unconnected-(M1-GPIO45-Pad41)") (class "Default")
      (node (ref "M1") (pin "41") (pinfunction "GPIO45_41") (pintype "passive+no_connect"))
    )
    (net (code "133") (name "unconnected-(M1-GPIO46-Pad44)") (class "Default")
      (node (ref "M1") (pin "44") (pinfunction "GPIO46_44") (pintype "passive+no_connect"))
    )
    (net (code "134") (name "unconnected-(M1-SPICLKNDIFF_GPIO48-Pad30)") (class "Default")
      (node (ref "M1") (pin "30") (pinfunction "SPICLKNDIFF_GPIO48_30") (pintype "passive+no_connect"))
    )
    (net (code "135") (name "unconnected-(M1-SPICLKPDIFF_GPIO47-Pad27)") (class "Default")
      (node (ref "M1") (pin "27") (pinfunction "SPICLKPDIFF_GPIO47_27") (pintype "passive+no_connect"))
    )
    (net (code "136") (name "unconnected-(M1-SPICS1_GPIO26-Pad26)") (class "Default")
      (node (ref "M1") (pin "26") (pinfunction "SPICS1_GPIO26_26") (pintype "passive+no_connect"))
    )
    (net (code "137") (name "unconnected-(M1-U1RXD_ADC2CH7_GPIO18-Pad22)") (class "Default")
      (node (ref "M1") (pin "22") (pinfunction "U1RXD_ADC2CH7_GPIO18_22") (pintype "passive+no_connect"))
    )
    (net (code "138") (name "unconnected-(M1-U1TXD_ADC2CH6_GPIO17-Pad21)") (class "Default")
      (node (ref "M1") (pin "21") (pinfunction "U1TXD_ADC2CH6_GPIO17_21") (pintype "passive+no_connect"))
    )
    (net (code "139") (name "unconnected-(M1-XTAL32KN_U0CTS_ADC2CH5_GPIO16-Pad20)") (class "Default")
      (node (ref "M1") (pin "20") (pinfunction "XTAL32KN_U0CTS_ADC2CH5_GPIO16_20") (pintype "passive+no_connect"))
    )
    (net (code "140") (name "unconnected-(M1-XTAL32KP_U0RTS_ADC2CH4_GPIO15-Pad19)") (class "Default")
      (node (ref "M1") (pin "19") (pinfunction "XTAL32KP_U0RTS_ADC2CH4_GPIO15_19") (pintype "passive+no_connect"))
    )
    (net (code "141") (name "unconnected-(U1-P214_INPUT_ONLY{slash}XCOUT-Pad7)") (class "Default")
      (node (ref "U1") (pin "7") (pinfunction "P214_INPUT_ONLY/XCOUT_7") (pintype "passive+no_connect"))
    )
    (net (code "142") (name "unconnected-(U1-P215_INPUT_ONLY{slash}XCIN-Pad6)") (class "Default")
      (node (ref "U1") (pin "6") (pinfunction "P215_INPUT_ONLY/XCIN_6") (pintype "passive+no_connect"))
    )
    (net (code "143") (name "unconnected-(U1-P402{slash}CRX0-Pad3)") (class "Default")
      (node (ref "U1") (pin "3") (pinfunction "P402/CRX0_3") (pintype "passive+no_connect"))
    )
    (net (code "144") (name "unconnected-(U1-P409{slash}GTIOC5A{slash}USB_EXICEN-Pad14)") (class "Default")
      (node (ref "U1") (pin "14") (pinfunction "P409/GTIOC5A/USB_EXICEN_14") (pintype "passive+no_connect"))
    )
    (net (code "145") (name "unconnected-(U3-PG-Pad8)") (class "Default")
      (node (ref "U3") (pin "8") (pinfunction "PG_8") (pintype "passive+no_connect"))
    )
  )
)
